# Low_Noise_100kHz_Oscilloscope_Preamplifi.net
KiCad netlist of a schematic drawn in Altium Designer
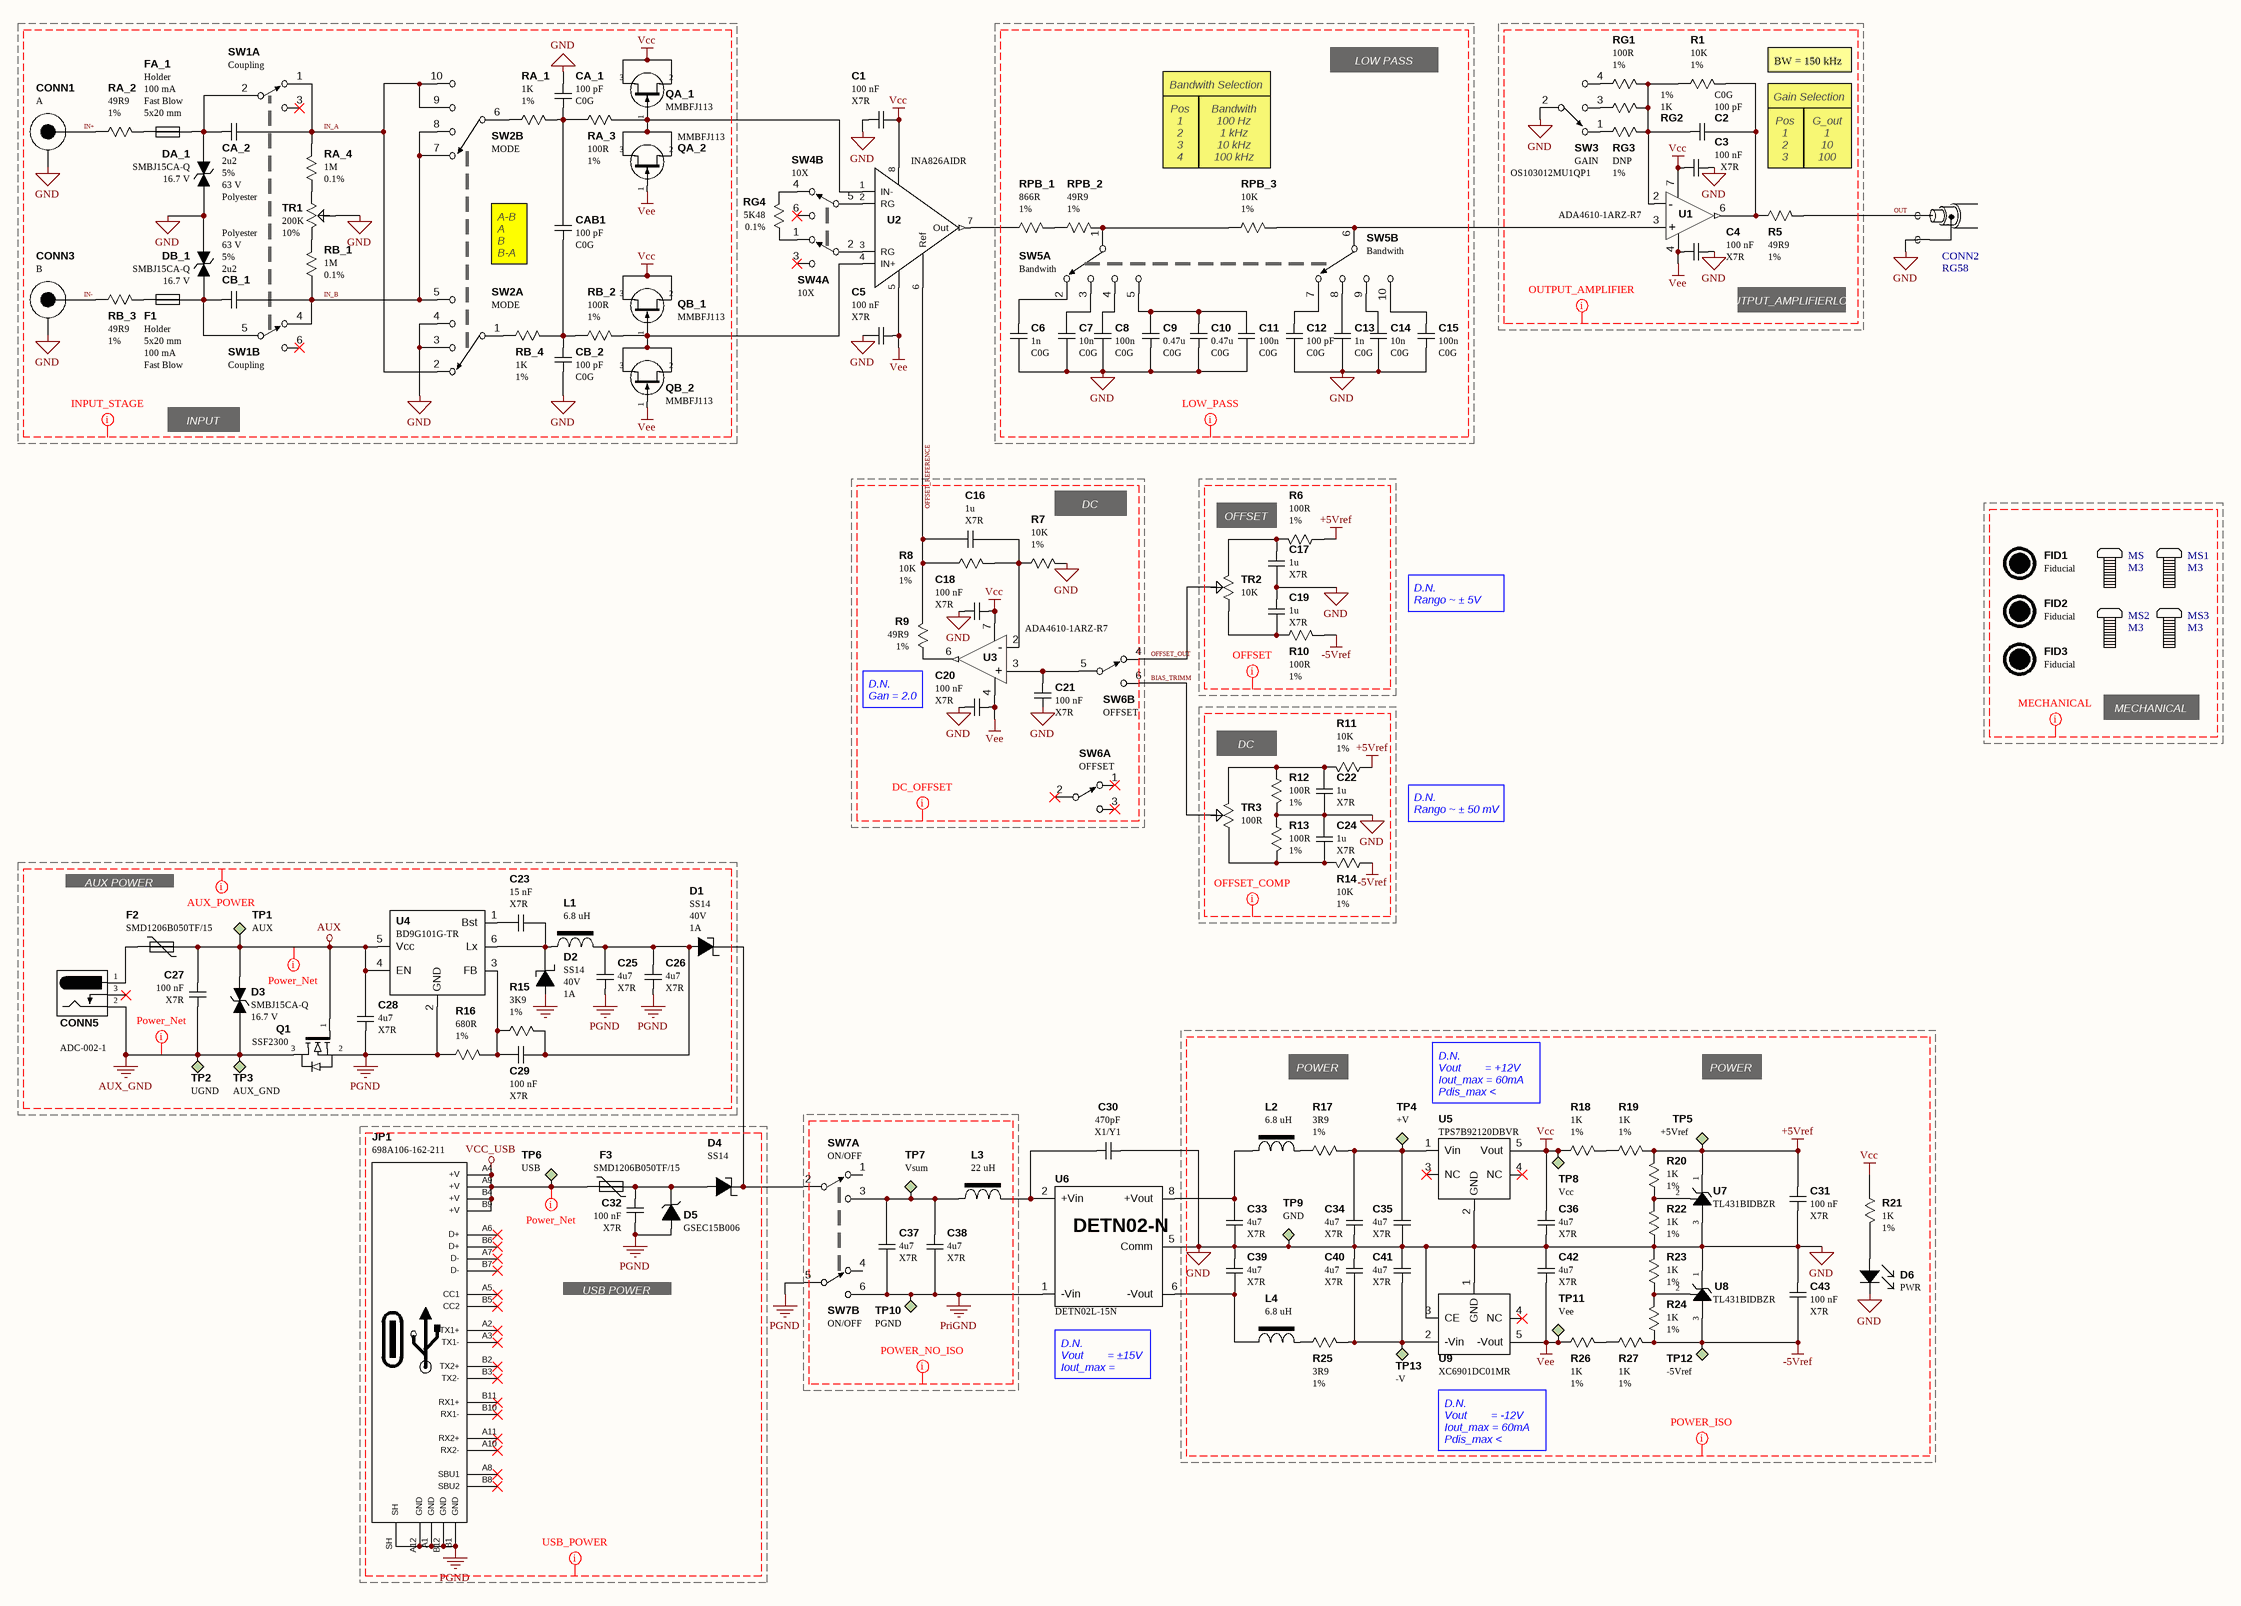
[diagram p0: Low_Noise_100kHz_Oscilloscope_Preamplifier.SchDoc]

(export (version "E")
  (design (tool "Eeschema 10.0.6"))
  (components
    (comp (ref "C1")
      (value "100 nF")
      (footprint "CAP_SMD_0603")
      (fields
        (field (name "04_MANUFACTURER PART NUMBER") "CC0603KRX7R9BB104")
        (field (name "05_DIGIKEY PART NUMBER") "311-1344-1-ND")
        (field (name "DIELECTRICO") "X7R")
      )
      (libsource (lib "Libreria_Altium") (part "Capacitor NP"))
    )
    (comp (ref "C2")
      (value "100 pF")
      (footprint "CAP_SMD_0603")
      (fields
        (field (name "04_MANUFACTURER PART NUMBER") "CC0603GRNPO9BN101")
        (field (name "05_DIGIKEY PART NUMBER") "311-3351-1-ND")
        (field (name "DIELECTRICO") "C0G")
      )
      (libsource (lib "Libreria_Altium") (part "Capacitor NP"))
    )
    (comp (ref "C3")
      (value "100 nF")
      (footprint "CAP_SMD_0603")
      (fields
        (field (name "04_MANUFACTURER PART NUMBER") "CC0603KRX7R9BB104")
        (field (name "05_DIGIKEY PART NUMBER") "311-1344-1-ND")
        (field (name "DIELECTRICO") "X7R")
      )
      (libsource (lib "Libreria_Altium") (part "Capacitor NP"))
    )
    (comp (ref "C4")
      (value "100 nF")
      (footprint "CAP_SMD_0603")
      (fields
        (field (name "04_MANUFACTURER PART NUMBER") "CC0603KRX7R9BB104")
        (field (name "05_DIGIKEY PART NUMBER") "311-1344-1-ND")
        (field (name "DIELECTRICO") "X7R")
      )
      (libsource (lib "Libreria_Altium") (part "Capacitor NP"))
    )
    (comp (ref "C5")
      (value "100 nF")
      (footprint "CAP_SMD_0603")
      (fields
        (field (name "04_MANUFACTURER PART NUMBER") "CC0603KRX7R9BB104")
        (field (name "05_DIGIKEY PART NUMBER") "311-1344-1-ND")
        (field (name "DIELECTRICO") "X7R")
      )
      (libsource (lib "Libreria_Altium") (part "Capacitor NP"))
    )
    (comp (ref "C6")
      (value "1n")
      (footprint "CAP_SMD_0603")
      (description "1000 pF ±2% 50V Ceramic Capacitor C0G, NP0 0603 (1608 Metric)")
      (fields
        (field (name "04_MANUFACTURER PART NUMBER") "CC0603GRNPO9BN102")
        (field (name "05_DIGIKEY PART NUMBER") "311-3916-1-ND")
        (field (name "DIELECTRICO") "C0G")
      )
      (libsource (lib "Libreria_Altium") (part "Capacitor NP"))
    )
    (comp (ref "C7")
      (value "10n")
      (footprint "CAP_SMD_0603")
      (description "10000 pF ±5% 50V Ceramic Capacitor C0G, NP0 0603 (1608 Metric)")
      (fields
        (field (name "04_MANUFACTURER PART NUMBER") "GRM1885C1H103JA01D")
        (field (name "05_DIGIKEY PART NUMBER") "490-9666-1-ND")
        (field (name "DIELECTRICO") "C0G")
      )
      (libsource (lib "Libreria_Altium") (part "Capacitor NP"))
    )
    (comp (ref "C8")
      (value "100n")
      (footprint "CAP_SMD_1206")
      (fields
        (field (name "04_MANUFACTURER PART NUMBER") "GRM3195C1H104JA05D")
        (field (name "05_DIGIKEY PART NUMBER") "490-GRM3195C1H104JA05DCT-ND")
        (field (name "DIELECTRICO") "C0G")
      )
      (libsource (lib "Libreria_Altium") (part "Capacitor NP"))
    )
    (comp (ref "C9")
      (value "0.47u")
      (footprint "CAP_SMD_1206")
      (description "0.47 µF ±5% 25V Ceramic Capacitor C0G, NP0 1206 (3216 Metric)")
      (fields
        (field (name "04_MANUFACTURER PART NUMBER") "GRM31C5C1E474JE01L")
        (field (name "05_DIGIKEY PART NUMBER") "490-GRM31C5C1E474JE01LCT-ND")
        (field (name "DIELECTRICO") "C0G")
      )
      (libsource (lib "Libreria_Altium") (part "Capacitor NP"))
    )
    (comp (ref "C10")
      (value "0.47u")
      (footprint "CAP_SMD_1206")
      (description "0.47 µF ±5% 25V Ceramic Capacitor C0G, NP0 1206 (3216 Metric)")
      (fields
        (field (name "04_MANUFACTURER PART NUMBER") "GRM31C5C1E474JE01L")
        (field (name "05_DIGIKEY PART NUMBER") "490-GRM31C5C1E474JE01LCT-ND")
        (field (name "DIELECTRICO") "C0G")
      )
      (libsource (lib "Libreria_Altium") (part "Capacitor NP"))
    )
    (comp (ref "C11")
      (value "100n")
      (footprint "CAP_SMD_1206")
      (fields
        (field (name "04_MANUFACTURER PART NUMBER") "GRM3195C1H104JA05D")
        (field (name "05_DIGIKEY PART NUMBER") "490-GRM3195C1H104JA05DCT-ND")
        (field (name "DIELECTRICO") "C0G")
      )
      (libsource (lib "Libreria_Altium") (part "Capacitor NP"))
    )
    (comp (ref "C12")
      (value "100 pF")
      (footprint "CAP_SMD_0603")
      (fields
        (field (name "04_MANUFACTURER PART NUMBER") "CC0603GRNPO9BN101")
        (field (name "05_DIGIKEY PART NUMBER") "311-3351-1-ND")
        (field (name "DIELECTRICO") "C0G")
      )
      (libsource (lib "Libreria_Altium") (part "Capacitor NP"))
    )
    (comp (ref "C13")
      (value "1n")
      (footprint "CAP_SMD_0603")
      (description "1000 pF ±2% 50V Ceramic Capacitor C0G, NP0 0603 (1608 Metric)")
      (fields
        (field (name "04_MANUFACTURER PART NUMBER") "CC0603GRNPO9BN102")
        (field (name "05_DIGIKEY PART NUMBER") "311-3916-1-ND")
        (field (name "DIELECTRICO") "C0G")
      )
      (libsource (lib "Libreria_Altium") (part "Capacitor NP"))
    )
    (comp (ref "C14")
      (value "10n")
      (footprint "CAP_SMD_0603")
      (description "10000 pF ±5% 50V Ceramic Capacitor C0G, NP0 0603 (1608 Metric)")
      (fields
        (field (name "04_MANUFACTURER PART NUMBER") "GRM1885C1H103JA01D")
        (field (name "05_DIGIKEY PART NUMBER") "490-9666-1-ND")
        (field (name "DIELECTRICO") "C0G")
      )
      (libsource (lib "Libreria_Altium") (part "Capacitor NP"))
    )
    (comp (ref "C15")
      (value "100n")
      (footprint "CAP_SMD_1206")
      (fields
        (field (name "04_MANUFACTURER PART NUMBER") "GRM3195C1H104JA05D")
        (field (name "05_DIGIKEY PART NUMBER") "490-GRM3195C1H104JA05DCT-ND")
        (field (name "DIELECTRICO") "C0G")
      )
      (libsource (lib "Libreria_Altium") (part "Capacitor NP"))
    )
    (comp (ref "C16")
      (value "1u")
      (footprint "CAP_SMD_0805")
      (fields
        (field (name "04_MANUFACTURER PART NUMBER") "CC0805JKX7R9BB105")
        (field (name "05_DIGIKEY PART NUMBER") "311-3498-1-ND")
        (field (name "DIELECTRICO") "X7R")
      )
      (libsource (lib "Libreria_Altium") (part "Capacitor NP"))
    )
    (comp (ref "C17")
      (value "1u")
      (footprint "CAP_SMD_0805")
      (fields
        (field (name "04_MANUFACTURER PART NUMBER") "CC0805JKX7R9BB105")
        (field (name "05_DIGIKEY PART NUMBER") "311-3498-1-ND")
        (field (name "DIELECTRICO") "X7R")
      )
      (libsource (lib "Libreria_Altium") (part "Capacitor NP"))
    )
    (comp (ref "C18")
      (value "100 nF")
      (footprint "CAP_SMD_0603")
      (fields
        (field (name "04_MANUFACTURER PART NUMBER") "CC0603KRX7R9BB104")
        (field (name "05_DIGIKEY PART NUMBER") "311-1344-1-ND")
        (field (name "DIELECTRICO") "X7R")
      )
      (libsource (lib "Libreria_Altium") (part "Capacitor NP"))
    )
    (comp (ref "C19")
      (value "1u")
      (footprint "CAP_SMD_0805")
      (fields
        (field (name "04_MANUFACTURER PART NUMBER") "CC0805JKX7R9BB105")
        (field (name "05_DIGIKEY PART NUMBER") "311-3498-1-ND")
        (field (name "DIELECTRICO") "X7R")
      )
      (libsource (lib "Libreria_Altium") (part "Capacitor NP"))
    )
    (comp (ref "C20")
      (value "100 nF")
      (footprint "CAP_SMD_0603")
      (fields
        (field (name "04_MANUFACTURER PART NUMBER") "CC0603KRX7R9BB104")
        (field (name "05_DIGIKEY PART NUMBER") "311-1344-1-ND")
        (field (name "DIELECTRICO") "X7R")
      )
      (libsource (lib "Libreria_Altium") (part "Capacitor NP"))
    )
    (comp (ref "C21")
      (value "100 nF")
      (footprint "CAP_SMD_0603")
      (fields
        (field (name "04_MANUFACTURER PART NUMBER") "CC0603KRX7R9BB104")
        (field (name "05_DIGIKEY PART NUMBER") "311-1344-1-ND")
        (field (name "DIELECTRICO") "X7R")
      )
      (libsource (lib "Libreria_Altium") (part "Capacitor NP"))
    )
    (comp (ref "C22")
      (value "1u")
      (footprint "CAP_SMD_0805")
      (fields
        (field (name "04_MANUFACTURER PART NUMBER") "CC0805JKX7R9BB105")
        (field (name "05_DIGIKEY PART NUMBER") "311-3498-1-ND")
        (field (name "DIELECTRICO") "X7R")
      )
      (libsource (lib "Libreria_Altium") (part "Capacitor NP"))
    )
    (comp (ref "C23")
      (value "15 nF")
      (footprint "CAP_SMD_0603")
      (description "0.1 µF ±10% 25V Ceramic Capacitor X7R 0603 (1608 Metric)")
      (fields
        (field (name "04_MANUFACTURER PART NUMBER") "CC0603KRX7R9BB153")
        (field (name "05_DIGIKEY PART NUMBER") "311-1430-1-ND")
        (field (name "DIELECTRICO") "X7R")
      )
      (libsource (lib "Libreria_Altium") (part "Capacitor NP"))
    )
    (comp (ref "C24")
      (value "1u")
      (footprint "CAP_SMD_0805")
      (fields
        (field (name "04_MANUFACTURER PART NUMBER") "CC0805JKX7R9BB105")
        (field (name "05_DIGIKEY PART NUMBER") "311-3498-1-ND")
        (field (name "DIELECTRICO") "X7R")
      )
      (libsource (lib "Libreria_Altium") (part "Capacitor NP"))
    )
    (comp (ref "C25")
      (value "4u7")
      (footprint "CAP_SMD_0805")
      (description "4.7 µF ±20% 50V Ceramic Capacitor X7R 0805 (2012 Metric)")
      (fields
        (field (name "04_MANUFACTURER PART NUMBER") "GRM21BZ71H475ME15K")
        (field (name "05_DIGIKEY PART NUMBER") "490-GRM21BZ71H475ME15KCT-ND")
        (field (name "DIELECTRICO") "X7R")
      )
      (libsource (lib "Libreria_Altium") (part "Capacitor NP"))
    )
    (comp (ref "C26")
      (value "4u7")
      (footprint "CAP_SMD_0805")
      (description "4.7 µF ±20% 50V Ceramic Capacitor X7R 0805 (2012 Metric)")
      (fields
        (field (name "04_MANUFACTURER PART NUMBER") "GRM21BZ71H475ME15K")
        (field (name "05_DIGIKEY PART NUMBER") "490-GRM21BZ71H475ME15KCT-ND")
        (field (name "DIELECTRICO") "X7R")
      )
      (libsource (lib "Libreria_Altium") (part "Capacitor NP"))
    )
    (comp (ref "C27")
      (value "100 nF")
      (footprint "CAP_SMD_0603")
      (description "0.1 µF ±10% 25V Ceramic Capacitor X7R 0603 (1608 Metric)")
      (fields
        (field (name "04_MANUFACTURER PART NUMBER") "CC0603KRX7R9BB104")
        (field (name "05_DIGIKEY PART NUMBER") "311-1344-1-ND")
        (field (name "DIELECTRICO") "X7R")
      )
      (libsource (lib "Libreria_Altium") (part "Capacitor NP"))
    )
    (comp (ref "C28")
      (value "4u7")
      (footprint "CAP_SMD_0805")
      (description "4.7 µF ±20% 50V Ceramic Capacitor X7R 0805 (2012 Metric)")
      (fields
        (field (name "04_MANUFACTURER PART NUMBER") "GRM21BZ71H475ME15K")
        (field (name "05_DIGIKEY PART NUMBER") "490-GRM21BZ71H475ME15KCT-ND")
        (field (name "DIELECTRICO") "X7R")
      )
      (libsource (lib "Libreria_Altium") (part "Capacitor NP"))
    )
    (comp (ref "C29")
      (value "100 nF")
      (footprint "CAP_SMD_0603")
      (description "0.1 µF ±10% 25V Ceramic Capacitor X7R 0603 (1608 Metric)")
      (fields
        (field (name "04_MANUFACTURER PART NUMBER") "CC0603KRX7R9BB104")
        (field (name "05_DIGIKEY PART NUMBER") "311-1344-1-ND")
        (field (name "DIELECTRICO") "X7R")
      )
      (libsource (lib "Libreria_Altium") (part "Capacitor NP"))
    )
    (comp (ref "C30")
      (value "470pF")
      (footprint "Capacitor_Radial_7.00mm")
      (description "470 pF ±10% 1500V (1.5kV) Ceramic Capacitor B Radial, Disc")
      (fields
        (field (name "04_MANUFACTURER PART NUMBER") "DE1B3RA471KN4AP01F")
        (field (name "05_DIGIKEY PART NUMBER") "490-16186-1-ND")
        (field (name "DIELECTRICO") "X1/Y1")
      )
      (libsource (lib "Libreria_Altium") (part "Capacitor NP"))
    )
    (comp (ref "C31")
      (value "100 nF")
      (footprint "CAP_SMD_0603")
      (fields
        (field (name "04_MANUFACTURER PART NUMBER") "CC0603KRX7R9BB104")
        (field (name "05_DIGIKEY PART NUMBER") "311-1344-1-ND")
        (field (name "DIELECTRICO") "X7R")
      )
      (libsource (lib "Libreria_Altium") (part "Capacitor NP"))
    )
    (comp (ref "C32")
      (value "100 nF")
      (footprint "CAP_SMD_0603")
      (description "0.1 µF ±10% 25V Ceramic Capacitor X7R 0603 (1608 Metric)")
      (fields
        (field (name "04_MANUFACTURER PART NUMBER") "CC0603KRX7R9BB104")
        (field (name "05_DIGIKEY PART NUMBER") "311-1344-1-ND")
        (field (name "DIELECTRICO") "X7R")
      )
      (libsource (lib "Libreria_Altium") (part "Capacitor NP"))
    )
    (comp (ref "C33")
      (value "4u7")
      (footprint "CAP_SMD_0805")
      (description "4.7 µF ±20% 50V Ceramic Capacitor X7R 0805 (2012 Metric)")
      (fields
        (field (name "04_MANUFACTURER PART NUMBER") "GRM21BZ71H475ME15K")
        (field (name "05_DIGIKEY PART NUMBER") "490-GRM21BZ71H475ME15KCT-ND")
        (field (name "DIELECTRICO") "X7R")
      )
      (libsource (lib "Libreria_Altium") (part "Capacitor NP"))
    )
    (comp (ref "C34")
      (value "4u7")
      (footprint "CAP_SMD_0805")
      (description "4.7 µF ±20% 50V Ceramic Capacitor X7R 0805 (2012 Metric)")
      (fields
        (field (name "04_MANUFACTURER PART NUMBER") "GRM21BZ71H475ME15K")
        (field (name "05_DIGIKEY PART NUMBER") "490-GRM21BZ71H475ME15KCT-ND")
        (field (name "DIELECTRICO") "X7R")
      )
      (libsource (lib "Libreria_Altium") (part "Capacitor NP"))
    )
    (comp (ref "C35")
      (value "4u7")
      (footprint "CAP_SMD_0805")
      (description "4.7 µF ±20% 50V Ceramic Capacitor X7R 0805 (2012 Metric)")
      (fields
        (field (name "04_MANUFACTURER PART NUMBER") "GRM21BZ71H475ME15K")
        (field (name "05_DIGIKEY PART NUMBER") "490-GRM21BZ71H475ME15KCT-ND")
        (field (name "DIELECTRICO") "X7R")
      )
      (libsource (lib "Libreria_Altium") (part "Capacitor NP"))
    )
    (comp (ref "C36")
      (value "4u7")
      (footprint "CAP_SMD_0805")
      (description "4.7 µF ±20% 50V Ceramic Capacitor X7R 0805 (2012 Metric)")
      (fields
        (field (name "04_MANUFACTURER PART NUMBER") "GRM21BZ71H475ME15K")
        (field (name "05_DIGIKEY PART NUMBER") "490-GRM21BZ71H475ME15KCT-ND")
        (field (name "DIELECTRICO") "X7R")
      )
      (libsource (lib "Libreria_Altium") (part "Capacitor NP"))
    )
    (comp (ref "C37")
      (value "4u7")
      (footprint "CAP_SMD_0805")
      (description "4.7 µF ±20% 50V Ceramic Capacitor X7R 0805 (2012 Metric)")
      (fields
        (field (name "04_MANUFACTURER PART NUMBER") "GRM21BZ71H475ME15K")
        (field (name "05_DIGIKEY PART NUMBER") "490-GRM21BZ71H475ME15KCT-ND")
        (field (name "DIELECTRICO") "X7R")
      )
      (libsource (lib "Libreria_Altium") (part "Capacitor NP"))
    )
    (comp (ref "C38")
      (value "4u7")
      (footprint "CAP_SMD_0805")
      (description "4.7 µF ±20% 50V Ceramic Capacitor X7R 0805 (2012 Metric)")
      (fields
        (field (name "04_MANUFACTURER PART NUMBER") "GRM21BZ71H475ME15K")
        (field (name "05_DIGIKEY PART NUMBER") "490-GRM21BZ71H475ME15KCT-ND")
        (field (name "DIELECTRICO") "X7R")
      )
      (libsource (lib "Libreria_Altium") (part "Capacitor NP"))
    )
    (comp (ref "C39")
      (value "4u7")
      (footprint "CAP_SMD_0805")
      (description "4.7 µF ±20% 50V Ceramic Capacitor X7R 0805 (2012 Metric)")
      (fields
        (field (name "04_MANUFACTURER PART NUMBER") "GRM21BZ71H475ME15K")
        (field (name "05_DIGIKEY PART NUMBER") "490-GRM21BZ71H475ME15KCT-ND")
        (field (name "DIELECTRICO") "X7R")
      )
      (libsource (lib "Libreria_Altium") (part "Capacitor NP"))
    )
    (comp (ref "C40")
      (value "4u7")
      (footprint "CAP_SMD_0805")
      (description "4.7 µF ±20% 50V Ceramic Capacitor X7R 0805 (2012 Metric)")
      (fields
        (field (name "04_MANUFACTURER PART NUMBER") "GRM21BZ71H475ME15K")
        (field (name "05_DIGIKEY PART NUMBER") "490-GRM21BZ71H475ME15KCT-ND")
        (field (name "DIELECTRICO") "X7R")
      )
      (libsource (lib "Libreria_Altium") (part "Capacitor NP"))
    )
    (comp (ref "C41")
      (value "4u7")
      (footprint "CAP_SMD_0805")
      (description "4.7 µF ±20% 50V Ceramic Capacitor X7R 0805 (2012 Metric)")
      (fields
        (field (name "04_MANUFACTURER PART NUMBER") "GRM21BZ71H475ME15K")
        (field (name "05_DIGIKEY PART NUMBER") "490-GRM21BZ71H475ME15KCT-ND")
        (field (name "DIELECTRICO") "X7R")
      )
      (libsource (lib "Libreria_Altium") (part "Capacitor NP"))
    )
    (comp (ref "C42")
      (value "4u7")
      (footprint "CAP_SMD_0805")
      (description "4.7 µF ±20% 50V Ceramic Capacitor X7R 0805 (2012 Metric)")
      (fields
        (field (name "04_MANUFACTURER PART NUMBER") "GRM21BZ71H475ME15K")
        (field (name "05_DIGIKEY PART NUMBER") "490-GRM21BZ71H475ME15KCT-ND")
        (field (name "DIELECTRICO") "X7R")
      )
      (libsource (lib "Libreria_Altium") (part "Capacitor NP"))
    )
    (comp (ref "C43")
      (value "100 nF")
      (footprint "CAP_SMD_0603")
      (fields
        (field (name "04_MANUFACTURER PART NUMBER") "CC0603KRX7R9BB104")
        (field (name "05_DIGIKEY PART NUMBER") "311-1344-1-ND")
        (field (name "DIELECTRICO") "X7R")
      )
      (libsource (lib "Libreria_Altium") (part "Capacitor NP"))
    )
    (comp (ref "CAB1")
      (value "100 pF")
      (footprint "CAP_SMD_0603")
      (fields
        (field (name "04_MANUFACTURER PART NUMBER") "CC0603GRNPO9BN101")
        (field (name "05_DIGIKEY PART NUMBER") "311-3351-1-ND")
        (field (name "DIELECTRICO") "C0G")
      )
      (libsource (lib "Libreria_Altium") (part "Capacitor NP"))
    )
    (comp (ref "CA_1")
      (value "100 pF")
      (footprint "CAP_SMD_0603")
      (fields
        (field (name "04_MANUFACTURER PART NUMBER") "CC0603GRNPO9BN101")
        (field (name "05_DIGIKEY PART NUMBER") "311-3351-1-ND")
        (field (name "DIELECTRICO") "C0G")
      )
      (libsource (lib "Libreria_Altium") (part "Capacitor NP"))
    )
    (comp (ref "CA_2")
      (value "2u2")
      (footprint "Capacitor_7.8x7.8x13")
      (fields
        (field (name "04_MANUFACTURER PART NUMBER") "B32529D0225J000")
        (field (name "05_DIGIKEY PART NUMBER") "495-1127-ND")
        (field (name "TOLERANCIA") "5%")
        (field (name "TENSIÓN") "63 V")
        (field (name "DIELECTRICO") "Polyester")
      )
      (libsource (lib "Libreria_Altium") (part "Capacitor NP"))
    )
    (comp (ref "CB_1")
      (value "2u2")
      (footprint "Capacitor_7.8x7.8x13")
      (fields
        (field (name "04_MANUFACTURER PART NUMBER") "B32529D0225J000")
        (field (name "05_DIGIKEY PART NUMBER") "495-1127-ND")
        (field (name "TOLERANCIA") "5%")
        (field (name "TENSIÓN") "63 V")
        (field (name "DIELECTRICO") "Polyester")
      )
      (libsource (lib "Libreria_Altium") (part "Capacitor NP"))
    )
    (comp (ref "CB_2")
      (value "100 pF")
      (footprint "CAP_SMD_0603")
      (fields
        (field (name "04_MANUFACTURER PART NUMBER") "CC0603GRNPO9BN101")
        (field (name "05_DIGIKEY PART NUMBER") "311-3351-1-ND")
        (field (name "DIELECTRICO") "C0G")
      )
      (libsource (lib "Libreria_Altium") (part "Capacitor NP"))
    )
    (comp (ref "CONN1")
      (value "A")
      (footprint "CONBNC002")
      (description "BNC Connector Jack, Female Socket 50 Ohms Panel Mount, Through Hole, Right Angle Solder")
      (fields
        (field (name "04_MANUFACTURER PART NUMBER") "CONBNC002")
        (field (name "05_DIGIKEY PART NUMBER") "343-CONBNC002-ND")
      )
      (libsource (lib "Libreria_Altium") (part "Conector BNC"))
    )
    (comp (ref "CONN2")
      (value "RG58")
      (footprint "Coaxial_RG58")
      (description "Cable RG58 Soldado directo a PCB")
      (libsource (lib "Libreria_Altium") (part "RG58_Coaxial_Cable"))
    )
    (comp (ref "CONN3")
      (value "B")
      (footprint "CONBNC002")
      (description "BNC Connector Jack, Female Socket 50 Ohms Panel Mount, Through Hole, Right Angle Solder")
      (fields
        (field (name "04_MANUFACTURER PART NUMBER") "CONBNC002")
        (field (name "05_DIGIKEY PART NUMBER") "343-CONBNC002-ND")
      )
      (libsource (lib "Libreria_Altium") (part "Conector BNC"))
    )
    (comp (ref "CONN5")
      (value "AUX")
      (footprint "ADC-002A")
      (description "DC JACK")
      (fields
        (field (name "04_MANUFACTURER PART NUMBER") "ADC-002-1")
        (field (name "05_DIGIKEY PART NUMBER") "2057-ADC-002-1-ND")
      )
      (libsource (lib "Libreria_Altium") (part "DC JACK"))
    )
    (comp (ref "D1")
      (value "SS14")
      (footprint "DO_214_AC")
      (description "Diode 40 V 1A Surface Mount DO-214AC (SMA)")
      (fields
        (field (name "04_MANUFACTURER PART NUMBER") "SS14-M3/5AT")
        (field (name "05_DIGIKEY PART NUMBER") "SS14-M3/5ATGICT-ND")
        (field (name "TENSIÓN") "40V")
        (field (name "CORRIENTE") "1A")
      )
      (libsource (lib "Libreria_Altium") (part "Diodo Schottky"))
    )
    (comp (ref "D2")
      (value "SS14")
      (footprint "DO_214_AC")
      (description "Diode 40 V 1A Surface Mount DO-214AC (SMA)")
      (fields
        (field (name "04_MANUFACTURER PART NUMBER") "SS14-M3/5AT")
        (field (name "05_DIGIKEY PART NUMBER") "SS14-M3/5ATGICT-ND")
        (field (name "TENSIÓN") "40V")
        (field (name "CORRIENTE") "1A")
      )
      (libsource (lib "Libreria_Altium") (part "Diodo Schottky"))
    )
    (comp (ref "D3")
      (value "SMBJ15CA-Q")
      (footprint "SOD_323")
      (description "24.4V Clamp 24.6A Ipp Tvs Diode Surface Mount DO-214AA (SMB)")
      (fields (field (name "05_DIGIKEY PART NUMBER") "118-SMBJ15CA-QCT-ND") (field (name "TENSIÓN") "16.7 V"))
      (libsource (lib "Libreria_Altium") (part "Diodo TVS Bidireccional"))
    )
    (comp (ref "D4")
      (value "SS14")
      (footprint "DO_214_AC")
      (description "Diode 40 V 1A Surface Mount DO-214AC (SMA)")
      (fields
        (field (name "04_MANUFACTURER PART NUMBER") "SS14-M3/5AT")
        (field (name "05_DIGIKEY PART NUMBER") "SS14-M3/5ATGICT-ND")
      )
      (libsource (lib "Libreria_Altium") (part "Diodo Schottky"))
    )
    (comp (ref "D5")
      (value "GSEC15B006")
      (footprint "SOD_323")
      (description "Diodo TVS")
      (fields (field (name "05_DIGIKEY PART NUMBER") "4786-GSEC15B006CT-ND"))
      (libsource (lib "Libreria_Altium") (part "Diodo TVS Unidireccional"))
    )
    (comp (ref "D6")
      (value "PWR")
      (footprint "LED_0603_1608")
      (description "Diodo LEd")
      (fields
        (field (name "04_MANUFACTURER PART NUMBER") "SML-D12U1WT86")
        (field (name "05_DIGIKEY PART NUMBER") "SML-D12U1WT86CT-ND")
      )
      (libsource (lib "Libreria_Altium") (part "Diodo LED"))
    )
    (comp (ref "DA_1")
      (value "SMBJ15CA-Q")
      (footprint "SOD_323")
      (description "24.4V Clamp 24.6A Ipp Tvs Diode Surface Mount DO-214AA (SMB)")
      (fields (field (name "05_DIGIKEY PART NUMBER") "118-SMBJ15CA-QCT-ND") (field (name "TENSIÓN") "16.7 V"))
      (libsource (lib "Libreria_Altium") (part "Diodo TVS Bidireccional"))
    )
    (comp (ref "DB_1")
      (value "SMBJ15CA-Q")
      (footprint "SOD_323")
      (description "24.4V Clamp 24.6A Ipp Tvs Diode Surface Mount DO-214AA (SMB)")
      (fields (field (name "05_DIGIKEY PART NUMBER") "118-SMBJ15CA-QCT-ND") (field (name "TENSIÓN") "16.7 V"))
      (libsource (lib "Libreria_Altium") (part "Diodo TVS Bidireccional"))
    )
    (comp (ref "F1")
      (value "Holder")
      (footprint "Porta Fusible 15x20")
      (description "Fuse Block 20 A 250V 1 Circuit Cartridge Through Hole")
      (fields
        (field (name "03_ENCAPSULADO") "5x20 mm")
        (field (name "04_MANUFACTURER PART NUMBER") "952017100001000")
        (field (name "05_DIGIKEY PART NUMBER") "732-952017100001000-ND")
        (field (name "CORRIENTE") "100 mA")
        (field (name "P_TYPE") "Fast Blow")
      )
      (libsource (lib "Libreria_Altium") (part "Fusible"))
    )
    (comp (ref "F2")
      (value "SMD1206B050TF/15")
      (footprint "RES_SMD_1210")
      (description "Polymeric PTC Resettable Fuse 15V 500 mA Ih Surface Mount 1206 (3216 Metric), Concave")
      (fields
        (field (name "04_MANUFACTURER PART NUMBER") "SMD1206B025TF/24")
        (field (name "05_DIGIKEY PART NUMBER") "13-SMD1206B025TF/24CT-ND")
      )
      (libsource (lib "Libreria_Altium") (part "Polyswitch"))
    )
    (comp (ref "F3")
      (value "SMD1206B050TF/15")
      (footprint "RES_SMD_1210")
      (description "Polymeric PTC Resettable Fuse 15V 500 mA Ih Surface Mount 1206 (3216 Metric), Concave")
      (fields
        (field (name "04_MANUFACTURER PART NUMBER") "SMD1206B025TF/24")
        (field (name "05_DIGIKEY PART NUMBER") "13-SMD1206B025TF/24CT-ND")
      )
      (libsource (lib "Libreria_Altium") (part "Polyswitch"))
    )
    (comp (ref "FA_1")
      (value "Holder")
      (footprint "Porta Fusible 15x20")
      (description "Fuse Block 20 A 250V 1 Circuit Cartridge Through Hole")
      (fields
        (field (name "03_ENCAPSULADO") "5x20 mm")
        (field (name "04_MANUFACTURER PART NUMBER") "952017100001000")
        (field (name "05_DIGIKEY PART NUMBER") "732-952017100001000-ND")
        (field (name "CORRIENTE") "100 mA")
        (field (name "P_TYPE") "Fast Blow")
      )
      (libsource (lib "Libreria_Altium") (part "Fusible"))
    )
    (comp (ref "FID1")
      (value "Fiducial")
      (footprint "Fiducial")
      (description "Fiducial SMD")
      (libsource (lib "Libreria_Altium") (part "Fiducial"))
    )
    (comp (ref "FID2")
      (value "Fiducial")
      (footprint "Fiducial")
      (description "Fiducial SMD")
      (libsource (lib "Libreria_Altium") (part "Fiducial"))
    )
    (comp (ref "FID3")
      (value "Fiducial")
      (footprint "Fiducial")
      (description "Fiducial SMD")
      (libsource (lib "Libreria_Altium") (part "Fiducial"))
    )
    (comp (ref "JP1")
      (value "698A106-162-211")
      (footprint "1054500101")
      (fields
        (field (name "04_MANUFACTURER PART NUMBER") "1054500101")
        (field (name "05_DIGIKEY PART NUMBER") "WM12856CT-ND")
      )
      (libsource (lib "Libreria_Altium") (part "USB C 3.0"))
    )
    (comp (ref "L1")
      (value "6.8 uH")
      (footprint "IND_SMD_6.0x6.0x4.5")
      (description "6.8 µH Shielded Wirewound Inductor 2.8 A 38mOhm Max 2424 (6060 Metric)")
      (fields
        (field (name "04_MANUFACTURER PART NUMBER") "IFSC2020DEER6R8M01")
        (field (name "05_DIGIKEY PART NUMBER") "541-IFSC2020DEER6R8M01CT-ND")
      )
      (libsource (lib "Libreria_Altium") (part "Inductor"))
    )
    (comp (ref "L2")
      (value "6.8 uH")
      (footprint "IND_SMD_6.0x6.0x4.5")
      (description "6.8 µH Shielded Wirewound Inductor 2.8 A 38mOhm Max 2424 (6060 Metric)")
      (fields
        (field (name "04_MANUFACTURER PART NUMBER") "IFSC2020DEER6R8M01")
        (field (name "05_DIGIKEY PART NUMBER") "541-IFSC2020DEER6R8M01CT-ND")
      )
      (libsource (lib "Libreria_Altium") (part "Inductor"))
    )
    (comp (ref "L3")
      (value "22 uH")
      (footprint "IND_SMD_12.7x12.7x6.5")
      (description "22 µH Shielded Drum Core, Wirewound Inductor 2.3 A 62mOhm Max Nonstandard")
      (fields
        (field (name "04_MANUFACTURER PART NUMBER") "SRR1206-220ML")
        (field (name "05_DIGIKEY PART NUMBER") "SRR1206-220MLCT-ND")
      )
      (libsource (lib "Libreria_Altium") (part "Inductor"))
    )
    (comp (ref "L4")
      (value "6.8 uH")
      (footprint "IND_SMD_6.0x6.0x4.5")
      (description "6.8 µH Shielded Wirewound Inductor 2.8 A 38mOhm Max 2424 (6060 Metric)")
      (fields
        (field (name "04_MANUFACTURER PART NUMBER") "IFSC2020DEER6R8M01")
        (field (name "05_DIGIKEY PART NUMBER") "541-IFSC2020DEER6R8M01CT-ND")
      )
      (libsource (lib "Libreria_Altium") (part "Inductor"))
    )
    (comp (ref "MS")
      (value "M3")
      (footprint "Fiducial")
      (description "Tornillo M3")
      (libsource (lib "Libreria_Altium") (part "Tornillo M3"))
    )
    (comp (ref "MS1")
      (value "M3")
      (footprint "Fiducial")
      (description "Tornillo M3")
      (libsource (lib "Libreria_Altium") (part "Tornillo M3"))
    )
    (comp (ref "MS2")
      (value "M3")
      (footprint "Fiducial")
      (description "Tornillo M3")
      (libsource (lib "Libreria_Altium") (part "Tornillo M3"))
    )
    (comp (ref "MS3")
      (value "M3")
      (footprint "Fiducial")
      (description "Tornillo M3")
      (libsource (lib "Libreria_Altium") (part "Tornillo M3"))
    )
    (comp (ref "Q1")
      (value "SSF2300")
      (footprint "SOT_23-3")
      (description "N-Channel MOSFET SOT-23")
      (fields
        (field (name "04_MANUFACTURER PART NUMBER") "AO3414A")
        (field (name "05_DIGIKEY PART NUMBER") "4518-AO3414ACT-ND")
      )
      (libsource (lib "Libreria_Altium") (part "NMOS"))
    )
    (comp (ref "QA_1")
      (value "MMBFJ113")
      (footprint "SOT_23-3")
      (description "JFET N-Channel 35 V 350 mW Surface Mount SOT-23-3")
      (fields (field (name "05_DIGIKEY PART NUMBER") "MMBFJ113CT-ND"))
      (libsource (lib "Libreria_Altium") (part "JFET"))
    )
    (comp (ref "QA_2")
      (value "MMBFJ113")
      (footprint "SOT_23-3")
      (description "JFET N-Channel 35 V 350 mW Surface Mount SOT-23-3")
      (fields (field (name "05_DIGIKEY PART NUMBER") "MMBFJ113CT-ND"))
      (libsource (lib "Libreria_Altium") (part "JFET"))
    )
    (comp (ref "QB_1")
      (value "MMBFJ113")
      (footprint "SOT_23-3")
      (description "JFET N-Channel 35 V 350 mW Surface Mount SOT-23-3")
      (fields (field (name "05_DIGIKEY PART NUMBER") "MMBFJ113CT-ND"))
      (libsource (lib "Libreria_Altium") (part "JFET"))
    )
    (comp (ref "QB_2")
      (value "MMBFJ113")
      (footprint "SOT_23-3")
      (description "JFET N-Channel 35 V 350 mW Surface Mount SOT-23-3")
      (fields (field (name "05_DIGIKEY PART NUMBER") "MMBFJ113CT-ND"))
      (libsource (lib "Libreria_Altium") (part "JFET"))
    )
    (comp (ref "R1")
      (value "10K")
      (footprint "RES_SMD_0603")
      (description "10 kOhms ±1% 0.1W, 1/10W Chip Resistor 0603 (1608 Metric) Thin Film")
      (fields
        (field (name "04_MANUFACTURER PART NUMBER") "RT0603FRE0710KL")
        (field (name "05_DIGIKEY PART NUMBER") "YAG2321CT-ND")
        (field (name "TOLERANCIA") "1%")
      )
      (libsource (lib "Libreria_Altium") (part "Resistor"))
    )
    (comp (ref "R5")
      (value "49R9")
      (footprint "RES_SMD_0603")
      (description "49.9 Ohms ±1% 0.1W, 1/10W Chip Resistor 0603 (1608 Metric) Thin Film")
      (fields
        (field (name "04_MANUFACTURER PART NUMBER") "RT0603FRD0749R9L")
        (field (name "05_DIGIKEY PART NUMBER") "13-RT0603FRD0749R9LCT-ND")
        (field (name "TOLERANCIA") "1%")
      )
      (libsource (lib "Libreria_Altium") (part "Resistor"))
    )
    (comp (ref "R6")
      (value "100R")
      (footprint "RES_SMD_0603")
      (description "100 Ohms ±1% 0.1W, 1/10W Chip Resistor 0603 (1608 Metric) Thin Film")
      (fields
        (field (name "04_MANUFACTURER PART NUMBER") "RT0603FRE13100RL")
        (field (name "05_DIGIKEY PART NUMBER") "13-RT0603FRE13100RLCT-ND")
        (field (name "TOLERANCIA") "1%")
      )
      (libsource (lib "Libreria_Altium") (part "Resistor"))
    )
    (comp (ref "R7")
      (value "10K")
      (footprint "RES_SMD_0603")
      (description "10 kOhms ±1% 0.1W, 1/10W Chip Resistor 0603 (1608 Metric) Thin Film")
      (fields
        (field (name "04_MANUFACTURER PART NUMBER") "RT0603FRE0710KL")
        (field (name "05_DIGIKEY PART NUMBER") "YAG2321CT-ND")
        (field (name "TOLERANCIA") "1%")
      )
      (libsource (lib "Libreria_Altium") (part "Resistor"))
    )
    (comp (ref "R8")
      (value "10K")
      (footprint "RES_SMD_0603")
      (description "10 kOhms ±1% 0.1W, 1/10W Chip Resistor 0603 (1608 Metric) Thin Film")
      (fields
        (field (name "04_MANUFACTURER PART NUMBER") "RT0603FRE0710KL")
        (field (name "05_DIGIKEY PART NUMBER") "YAG2321CT-ND")
        (field (name "TOLERANCIA") "1%")
      )
      (libsource (lib "Libreria_Altium") (part "Resistor"))
    )
    (comp (ref "R9")
      (value "49R9")
      (footprint "RES_SMD_0603")
      (description "49.9 Ohms ±1% 0.1W, 1/10W Chip Resistor 0603 (1608 Metric) Thin Film")
      (fields
        (field (name "04_MANUFACTURER PART NUMBER") "RT0603FRD0749R9L")
        (field (name "05_DIGIKEY PART NUMBER") "13-RT0603FRD0749R9LCT-ND")
        (field (name "TOLERANCIA") "1%")
      )
      (libsource (lib "Libreria_Altium") (part "Resistor"))
    )
    (comp (ref "R10")
      (value "100R")
      (footprint "RES_SMD_0603")
      (description "100 Ohms ±1% 0.1W, 1/10W Chip Resistor 0603 (1608 Metric) Thin Film")
      (fields
        (field (name "04_MANUFACTURER PART NUMBER") "RT0603FRE13100RL")
        (field (name "05_DIGIKEY PART NUMBER") "13-RT0603FRE13100RLCT-ND")
        (field (name "TOLERANCIA") "1%")
      )
      (libsource (lib "Libreria_Altium") (part "Resistor"))
    )
    (comp (ref "R11")
      (value "10K")
      (footprint "RES_SMD_0603")
      (description "10 kOhms ±1% 0.1W, 1/10W Chip Resistor 0603 (1608 Metric) Thin Film")
      (fields
        (field (name "04_MANUFACTURER PART NUMBER") "RT0603FRE0710KL")
        (field (name "05_DIGIKEY PART NUMBER") "YAG2321CT-ND")
        (field (name "TOLERANCIA") "1%")
      )
      (libsource (lib "Libreria_Altium") (part "Resistor"))
    )
    (comp (ref "R12")
      (value "100R")
      (footprint "RES_SMD_0603")
      (description "100 Ohms ±1% 0.1W, 1/10W Chip Resistor 0603 (1608 Metric) Thin Film")
      (fields
        (field (name "04_MANUFACTURER PART NUMBER") "RT0603FRE13100RL")
        (field (name "05_DIGIKEY PART NUMBER") "13-RT0603FRE13100RLCT-ND")
        (field (name "TOLERANCIA") "1%")
      )
      (libsource (lib "Libreria_Altium") (part "Resistor"))
    )
    (comp (ref "R13")
      (value "100R")
      (footprint "RES_SMD_0603")
      (description "100 Ohms ±1% 0.1W, 1/10W Chip Resistor 0603 (1608 Metric) Thin Film")
      (fields
        (field (name "04_MANUFACTURER PART NUMBER") "RT0603FRE13100RL")
        (field (name "05_DIGIKEY PART NUMBER") "13-RT0603FRE13100RLCT-ND")
        (field (name "TOLERANCIA") "1%")
      )
      (libsource (lib "Libreria_Altium") (part "Resistor"))
    )
    (comp (ref "R14")
      (value "10K")
      (footprint "RES_SMD_0603")
      (description "10 kOhms ±1% 0.1W, 1/10W Chip Resistor 0603 (1608 Metric) Thin Film")
      (fields
        (field (name "04_MANUFACTURER PART NUMBER") "RT0603FRE0710KL")
        (field (name "05_DIGIKEY PART NUMBER") "YAG2321CT-ND")
        (field (name "TOLERANCIA") "1%")
      )
      (libsource (lib "Libreria_Altium") (part "Resistor"))
    )
    (comp (ref "R15")
      (value "3K9")
      (footprint "RES_SMD_0603")
      (description "3.9 kOhms ±1% 0.1W, 1/10W Chip Resistor 0603 (1608 Metric) Thick Film")
      (fields
        (field (name "04_MANUFACTURER PART NUMBER") "RC0603FR-133K9L")
        (field (name "05_DIGIKEY PART NUMBER") "13-RC0603FR-133K9LCT-ND")
        (field (name "TOLERANCIA") "1%")
      )
      (libsource (lib "Libreria_Altium") (part "Resistor"))
    )
    (comp (ref "R16")
      (value "680R")
      (footprint "RES_SMD_0603")
      (description "680 Ohms ±1% 0.1W, 1/10W Chip Resistor 0603 (1608 Metric) Moisture Resistant Thick Film")
      (fields
        (field (name "04_MANUFACTURER PART NUMBER") "RC0603FR-07680RL")
        (field (name "05_DIGIKEY PART NUMBER") "311-680HRCT-ND")
        (field (name "TOLERANCIA") "1%")
      )
      (libsource (lib "Libreria_Altium") (part "Resistor"))
    )
    (comp (ref "R17")
      (value "3R9")
      (footprint "RES_SMD_0603")
      (fields
        (field (name "04_MANUFACTURER PART NUMBER") "RT0603FRE073R9L")
        (field (name "05_DIGIKEY PART NUMBER") "13-RT0603FRE073R9LCT-ND")
        (field (name "TOLERANCIA") "1%")
      )
      (libsource (lib "Libreria_Altium") (part "Resistor"))
    )
    (comp (ref "R18")
      (value "1K")
      (footprint "RES_SMD_0603")
      (description "1 kOhms ±1% 0.1W, 1/10W Chip Resistor 0603 (1608 Metric) Thin Film")
      (fields
        (field (name "04_MANUFACTURER PART NUMBER") "RT0603FRE131KL")
        (field (name "05_DIGIKEY PART NUMBER") "13-RT0603FRE131KLCT-ND")
        (field (name "TOLERANCIA") "1%")
      )
      (libsource (lib "Libreria_Altium") (part "Resistor"))
    )
    (comp (ref "R19")
      (value "1K")
      (footprint "RES_SMD_0603")
      (description "1 kOhms ±1% 0.1W, 1/10W Chip Resistor 0603 (1608 Metric) Thin Film")
      (fields
        (field (name "04_MANUFACTURER PART NUMBER") "RT0603FRE131KL")
        (field (name "05_DIGIKEY PART NUMBER") "13-RT0603FRE131KLCT-ND")
        (field (name "TOLERANCIA") "1%")
      )
      (libsource (lib "Libreria_Altium") (part "Resistor"))
    )
    (comp (ref "R20")
      (value "1K")
      (footprint "RES_SMD_0603")
      (description "1 kOhms ±1% 0.1W, 1/10W Chip Resistor 0603 (1608 Metric) Thin Film")
      (fields
        (field (name "04_MANUFACTURER PART NUMBER") "RT0603FRE131KL")
        (field (name "05_DIGIKEY PART NUMBER") "13-RT0603FRE131KLCT-ND")
        (field (name "TOLERANCIA") "1%")
      )
      (libsource (lib "Libreria_Altium") (part "Resistor"))
    )
    (comp (ref "R21")
      (value "1K")
      (footprint "RES_SMD_0603")
      (description "1 kOhms ±1% 0.1W, 1/10W Chip Resistor 0603 (1608 Metric) Thin Film")
      (fields
        (field (name "04_MANUFACTURER PART NUMBER") "RT0603FRE131KL")
        (field (name "05_DIGIKEY PART NUMBER") "13-RT0603FRE131KLCT-ND")
        (field (name "TOLERANCIA") "1%")
      )
      (libsource (lib "Libreria_Altium") (part "Resistor"))
    )
    (comp (ref "R22")
      (value "1K")
      (footprint "RES_SMD_0603")
      (description "1 kOhms ±1% 0.1W, 1/10W Chip Resistor 0603 (1608 Metric) Thin Film")
      (fields
        (field (name "04_MANUFACTURER PART NUMBER") "RT0603FRE131KL")
        (field (name "05_DIGIKEY PART NUMBER") "13-RT0603FRE131KLCT-ND")
        (field (name "TOLERANCIA") "1%")
      )
      (libsource (lib "Libreria_Altium") (part "Resistor"))
    )
    (comp (ref "R23")
      (value "1K")
      (footprint "RES_SMD_0603")
      (description "1 kOhms ±1% 0.1W, 1/10W Chip Resistor 0603 (1608 Metric) Thin Film")
      (fields
        (field (name "04_MANUFACTURER PART NUMBER") "RT0603FRE131KL")
        (field (name "05_DIGIKEY PART NUMBER") "13-RT0603FRE131KLCT-ND")
        (field (name "TOLERANCIA") "1%")
      )
      (libsource (lib "Libreria_Altium") (part "Resistor"))
    )
    (comp (ref "R24")
      (value "1K")
      (footprint "RES_SMD_0603")
      (description "1 kOhms ±1% 0.1W, 1/10W Chip Resistor 0603 (1608 Metric) Thin Film")
      (fields
        (field (name "04_MANUFACTURER PART NUMBER") "RT0603FRE131KL")
        (field (name "05_DIGIKEY PART NUMBER") "13-RT0603FRE131KLCT-ND")
        (field (name "TOLERANCIA") "1%")
      )
      (libsource (lib "Libreria_Altium") (part "Resistor"))
    )
    (comp (ref "R25")
      (value "3R9")
      (footprint "RES_SMD_0603")
      (fields
        (field (name "04_MANUFACTURER PART NUMBER") "RT0603FRE073R9L")
        (field (name "05_DIGIKEY PART NUMBER") "13-RT0603FRE073R9LCT-ND")
        (field (name "TOLERANCIA") "1%")
      )
      (libsource (lib "Libreria_Altium") (part "Resistor"))
    )
    (comp (ref "R26")
      (value "1K")
      (footprint "RES_SMD_0603")
      (description "1 kOhms ±1% 0.1W, 1/10W Chip Resistor 0603 (1608 Metric) Thin Film")
      (fields
        (field (name "04_MANUFACTURER PART NUMBER") "RT0603FRE131KL")
        (field (name "05_DIGIKEY PART NUMBER") "13-RT0603FRE131KLCT-ND")
        (field (name "TOLERANCIA") "1%")
      )
      (libsource (lib "Libreria_Altium") (part "Resistor"))
    )
    (comp (ref "R27")
      (value "1K")
      (footprint "RES_SMD_0603")
      (description "1 kOhms ±1% 0.1W, 1/10W Chip Resistor 0603 (1608 Metric) Thin Film")
      (fields
        (field (name "04_MANUFACTURER PART NUMBER") "RT0603FRE131KL")
        (field (name "05_DIGIKEY PART NUMBER") "13-RT0603FRE131KLCT-ND")
        (field (name "TOLERANCIA") "1%")
      )
      (libsource (lib "Libreria_Altium") (part "Resistor"))
    )
    (comp (ref "RA_1")
      (value "1K")
      (footprint "RES_SMD_0603")
      (description "1 kOhms ±1% 0.1W, 1/10W Chip Resistor 0603 (1608 Metric) Thin Film")
      (fields
        (field (name "04_MANUFACTURER PART NUMBER") "RT0603FRE131KL")
        (field (name "05_DIGIKEY PART NUMBER") "13-RT0603FRE131KLCT-ND")
        (field (name "TOLERANCIA") "1%")
      )
      (libsource (lib "Libreria_Altium") (part "Resistor"))
    )
    (comp (ref "RA_2")
      (value "49R9")
      (footprint "RES_SMD_0603")
      (description "49.9 Ohms ±1% 0.1W, 1/10W Chip Resistor 0603 (1608 Metric) Thin Film")
      (fields
        (field (name "04_MANUFACTURER PART NUMBER") "RT0603FRD0749R9L")
        (field (name "05_DIGIKEY PART NUMBER") "13-RT0603FRD0749R9LCT-ND")
        (field (name "TOLERANCIA") "1%")
      )
      (libsource (lib "Libreria_Altium") (part "Resistor"))
    )
    (comp (ref "RA_3")
      (value "100R")
      (footprint "RES_SMD_0603")
      (description "100 Ohms ±1% 0.1W, 1/10W Chip Resistor 0603 (1608 Metric) Thin Film")
      (fields
        (field (name "04_MANUFACTURER PART NUMBER") "RT0603FRE13100RL")
        (field (name "05_DIGIKEY PART NUMBER") "13-RT0603FRE13100RLCT-ND")
        (field (name "TOLERANCIA") "1%")
      )
      (libsource (lib "Libreria_Altium") (part "Resistor"))
    )
    (comp (ref "RA_4")
      (value "1M")
      (footprint "RES_SMD_0603")
      (description "499 kOhms ±1% 0.1W, 1/10W Chip Resistor 0603 (1608 Metric) Thin Film")
      (fields
        (field (name "04_MANUFACTURER PART NUMBER") "RT0603BRD071ML")
        (field (name "05_DIGIKEY PART NUMBER") "YAG4498CT-ND")
        (field (name "TOLERANCIA") "0.1%")
      )
      (libsource (lib "Libreria_Altium") (part "Resistor"))
    )
    (comp (ref "RB_1")
      (value "1M")
      (footprint "RES_SMD_0603")
      (description "499 kOhms ±1% 0.1W, 1/10W Chip Resistor 0603 (1608 Metric) Thin Film")
      (fields
        (field (name "04_MANUFACTURER PART NUMBER") "RT0603BRD071ML")
        (field (name "05_DIGIKEY PART NUMBER") "YAG4498CT-ND")
        (field (name "TOLERANCIA") "0.1%")
      )
      (libsource (lib "Libreria_Altium") (part "Resistor"))
    )
    (comp (ref "RB_2")
      (value "100R")
      (footprint "RES_SMD_0603")
      (description "100 Ohms ±1% 0.1W, 1/10W Chip Resistor 0603 (1608 Metric) Thin Film")
      (fields
        (field (name "04_MANUFACTURER PART NUMBER") "RT0603FRE13100RL")
        (field (name "05_DIGIKEY PART NUMBER") "13-RT0603FRE13100RLCT-ND")
        (field (name "TOLERANCIA") "1%")
      )
      (libsource (lib "Libreria_Altium") (part "Resistor"))
    )
    (comp (ref "RB_3")
      (value "49R9")
      (footprint "RES_SMD_0603")
      (description "49.9 Ohms ±1% 0.1W, 1/10W Chip Resistor 0603 (1608 Metric) Thin Film")
      (fields
        (field (name "04_MANUFACTURER PART NUMBER") "RT0603FRD0749R9L")
        (field (name "05_DIGIKEY PART NUMBER") "13-RT0603FRD0749R9LCT-ND")
        (field (name "TOLERANCIA") "1%")
      )
      (libsource (lib "Libreria_Altium") (part "Resistor"))
    )
    (comp (ref "RB_4")
      (value "1K")
      (footprint "RES_SMD_0603")
      (description "1 kOhms ±1% 0.1W, 1/10W Chip Resistor 0603 (1608 Metric) Thin Film")
      (fields
        (field (name "04_MANUFACTURER PART NUMBER") "RT0603FRE131KL")
        (field (name "05_DIGIKEY PART NUMBER") "13-RT0603FRE131KLCT-ND")
        (field (name "TOLERANCIA") "1%")
      )
      (libsource (lib "Libreria_Altium") (part "Resistor"))
    )
    (comp (ref "RG1")
      (value "100R")
      (footprint "RES_SMD_0603")
      (description "100 Ohms ±1% 0.1W, 1/10W Chip Resistor 0603 (1608 Metric) Thin Film")
      (fields
        (field (name "04_MANUFACTURER PART NUMBER") "RT0603FRE13100RL")
        (field (name "05_DIGIKEY PART NUMBER") "13-RT0603FRE13100RLCT-ND")
        (field (name "TOLERANCIA") "1%")
      )
      (libsource (lib "Libreria_Altium") (part "Resistor"))
    )
    (comp (ref "RG2")
      (value "1K")
      (footprint "RES_SMD_0603")
      (description "1 kOhms ±1% 0.1W, 1/10W Chip Resistor 0603 (1608 Metric) Thin Film")
      (fields
        (field (name "04_MANUFACTURER PART NUMBER") "RT0603FRE131KL")
        (field (name "05_DIGIKEY PART NUMBER") "13-RT0603FRE131KLCT-ND")
        (field (name "TOLERANCIA") "1%")
      )
      (libsource (lib "Libreria_Altium") (part "Resistor"))
    )
    (comp (ref "RG3")
      (value "DNP")
      (footprint "RES_SMD_0603")
      (description "100 Ohms ±1% 0.1W, 1/10W Chip Resistor 0603 (1608 Metric) Thin Film")
      (fields
        (field (name "04_MANUFACTURER PART NUMBER") "RT0603FRE13100RL")
        (field (name "05_DIGIKEY PART NUMBER") "13-RT0603FRE13100RLCT-ND")
        (field (name "TOLERANCIA") "1%")
      )
      (libsource (lib "Libreria_Altium") (part "Resistor"))
    )
    (comp (ref "RG4")
      (value "5K48")
      (footprint "RES_SMD_0603")
      (description "5.49 kOhms ±0.1% 0.1W, 1/10W Chip Resistor 0603 (1608 Metric) Thin Film")
      (fields
        (field (name "04_MANUFACTURER PART NUMBER") "RT0603BRD075K49L")
        (field (name "05_DIGIKEY PART NUMBER") "YAG1698CT-ND")
        (field (name "TOLERANCIA") "0.1%")
      )
      (libsource (lib "Libreria_Altium") (part "Resistor"))
    )
    (comp (ref "RPB_1")
      (value "866R")
      (footprint "RES_SMD_0603")
      (description "866 Ohms ±1% 0.1W, 1/10W Chip Resistor 0603 (1608 Metric) Thin Film")
      (fields
        (field (name "04_MANUFACTURER PART NUMBER") "RT0603FRE07866RL")
        (field (name "05_DIGIKEY PART NUMBER") "13-RT0603FRE07866RLCT-ND")
        (field (name "TOLERANCIA") "1%")
      )
      (libsource (lib "Libreria_Altium") (part "Resistor"))
    )
    (comp (ref "RPB_2")
      (value "49R9")
      (footprint "RES_SMD_0603")
      (description "49.9 Ohms ±1% 0.1W, 1/10W Chip Resistor 0603 (1608 Metric) Thin Film")
      (fields
        (field (name "04_MANUFACTURER PART NUMBER") "RT0603FRD0749R9L")
        (field (name "05_DIGIKEY PART NUMBER") "13-RT0603FRD0749R9LCT-ND")
        (field (name "TOLERANCIA") "1%")
      )
      (libsource (lib "Libreria_Altium") (part "Resistor"))
    )
    (comp (ref "RPB_3")
      (value "10K")
      (footprint "RES_SMD_0603")
      (description "10 kOhms ±1% 0.1W, 1/10W Chip Resistor 0603 (1608 Metric) Thin Film")
      (fields
        (field (name "04_MANUFACTURER PART NUMBER") "RT0603FRE0710KL")
        (field (name "05_DIGIKEY PART NUMBER") "YAG2321CT-ND")
        (field (name "TOLERANCIA") "1%")
      )
      (libsource (lib "Libreria_Altium") (part "Resistor"))
    )
    (comp (ref "SW1")
      (value "Coupling")
      (footprint "MFS201N-9-Z")
      (description "Slide Switch SPDT  90° Through Hole")
      (fields
        (field (name "04_MANUFACTURER PART NUMBER") "MFS201N-9-Z")
        (field (name "05_DIGIKEY PART NUMBER") "563-1565-ND")
      )
      (libsource (lib "Libreria_Altium") (part "Interruptor DPDT"))
    )
    (comp (ref "SW2")
      (value "MODE")
      (footprint "HASS0399")
      (description "SWITCH SLIDE DP4T 300MA 30V")
      (fields
        (field (name "04_MANUFACTURER PART NUMBER") "HASS0399")
        (field (name "05_DIGIKEY PART NUMBER") "CKN10394-ND")
      )
      (libsource (lib "Libreria_Altium") (part "Interruptor 2P4T"))
    )
    (comp (ref "SW3")
      (value "GAIN")
      (footprint "OS103012MU1QP1")
      (description "Slide Switch SP3T Through Hole")
      (fields
        (field (name "04_MANUFACTURER PART NUMBER") "OS103012MU1QP1")
        (field (name "05_DIGIKEY PART NUMBER") "CKN9552-ND")
      )
      (libsource (lib "Libreria_Altium") (part "Interruptor SP3T"))
    )
    (comp (ref "SW4")
      (value "10X")
      (footprint "MFS201N-9-Z")
      (description "Slide Switch SPDT  90° Through Hole")
      (fields
        (field (name "04_MANUFACTURER PART NUMBER") "MFS201N-9-Z")
        (field (name "05_DIGIKEY PART NUMBER") "563-1565-ND")
      )
      (libsource (lib "Libreria_Altium") (part "Interruptor DPDT"))
    )
    (comp (ref "SW5")
      (value "Bandwith")
      (footprint "HASS0399")
      (description "SWITCH SLIDE DP4T 300MA 30V")
      (fields
        (field (name "04_MANUFACTURER PART NUMBER") "HASS0399")
        (field (name "05_DIGIKEY PART NUMBER") "CKN10394-ND")
      )
      (libsource (lib "Libreria_Altium") (part "Interruptor 2P4T"))
    )
    (comp (ref "SW6")
      (value "OFFSET")
      (footprint "MFS201N-9-Z")
      (description "Slide Switch SPDT  90° Through Hole")
      (fields
        (field (name "04_MANUFACTURER PART NUMBER") "MFS201N-9-Z")
        (field (name "05_DIGIKEY PART NUMBER") "563-1565-ND")
      )
      (libsource (lib "Libreria_Altium") (part "Interruptor DPDT"))
    )
    (comp (ref "SW7")
      (value "ON/OFF")
      (footprint "MFS201N-9-Z")
      (description "Slide Switch SPDT  90° Through Hole")
      (fields
        (field (name "04_MANUFACTURER PART NUMBER") "MFS201N-9-Z")
        (field (name "05_DIGIKEY PART NUMBER") "563-1565-ND")
      )
      (libsource (lib "Libreria_Altium") (part "Interruptor DPDT"))
    )
    (comp (ref "TP1")
      (value "AUX")
      (footprint "Test_Point_THT")
      (description "Testpoint")
      (fields (field (name "04_MANUFACTURER PART NUMBER") "NA"))
      (libsource (lib "Libreria_Altium") (part "TestPoint_SMD"))
    )
    (comp (ref "TP2")
      (value "UGND")
      (footprint "Test_Point_THT")
      (description "Testpoint")
      (fields (field (name "04_MANUFACTURER PART NUMBER") "NA"))
      (libsource (lib "Libreria_Altium") (part "TestPoint_SMD"))
    )
    (comp (ref "TP3")
      (value "AUX_GND")
      (footprint "Test_Point_THT")
      (description "Testpoint")
      (fields (field (name "04_MANUFACTURER PART NUMBER") "NA"))
      (libsource (lib "Libreria_Altium") (part "TestPoint_SMD"))
    )
    (comp (ref "TP4")
      (value "+V")
      (footprint "Test_Point_THT")
      (description "Testpoint")
      (fields (field (name "04_MANUFACTURER PART NUMBER") "NA"))
      (libsource (lib "Libreria_Altium") (part "TestPoint_SMD"))
    )
    (comp (ref "TP5")
      (value "+5Vref")
      (footprint "Test_Point_THT")
      (description "Testpoint")
      (fields (field (name "04_MANUFACTURER PART NUMBER") "NA"))
      (libsource (lib "Libreria_Altium") (part "TestPoint_SMD"))
    )
    (comp (ref "TP6")
      (value "USB")
      (footprint "Test_Point_THT")
      (description "Testpoint")
      (fields (field (name "04_MANUFACTURER PART NUMBER") "NA"))
      (libsource (lib "Libreria_Altium") (part "TestPoint_SMD"))
    )
    (comp (ref "TP7")
      (value "Vsum")
      (footprint "Test_Point_THT")
      (description "Testpoint")
      (fields (field (name "04_MANUFACTURER PART NUMBER") "NA"))
      (libsource (lib "Libreria_Altium") (part "TestPoint_SMD"))
    )
    (comp (ref "TP8")
      (value "Vcc")
      (footprint "Test_Point_THT")
      (description "Testpoint")
      (fields (field (name "04_MANUFACTURER PART NUMBER") "NA"))
      (libsource (lib "Libreria_Altium") (part "TestPoint_SMD"))
    )
    (comp (ref "TP9")
      (value "GND")
      (footprint "Test_Point_THT")
      (description "Testpoint")
      (fields (field (name "04_MANUFACTURER PART NUMBER") "NA"))
      (libsource (lib "Libreria_Altium") (part "TestPoint_SMD"))
    )
    (comp (ref "TP10")
      (value "PGND")
      (footprint "Test_Point_THT")
      (description "Testpoint")
      (fields (field (name "04_MANUFACTURER PART NUMBER") "NA"))
      (libsource (lib "Libreria_Altium") (part "TestPoint_SMD"))
    )
    (comp (ref "TP11")
      (value "Vee")
      (footprint "Test_Point_THT")
      (description "Testpoint")
      (fields (field (name "04_MANUFACTURER PART NUMBER") "NA"))
      (libsource (lib "Libreria_Altium") (part "TestPoint_SMD"))
    )
    (comp (ref "TP12")
      (value "-5Vref")
      (footprint "Test_Point_THT")
      (description "Testpoint")
      (fields (field (name "04_MANUFACTURER PART NUMBER") "NA"))
      (libsource (lib "Libreria_Altium") (part "TestPoint_SMD"))
    )
    (comp (ref "TP13")
      (value "-V")
      (footprint "Test_Point_THT")
      (description "Testpoint")
      (fields (field (name "04_MANUFACTURER PART NUMBER") "NA"))
      (libsource (lib "Libreria_Altium") (part "TestPoint_SMD"))
    )
    (comp (ref "TR1")
      (value "200K")
      (footprint "Trimpot J-Lead")
      (description "1 kOhms 0.25W, 1/4W J Lead Surface Mount Trimmer Potentiometer Cermet 11.0 Turn Top Adjustment")
      (fields
        (field (name "04_MANUFACTURER PART NUMBER") "PVG5A204C03R00")
        (field (name "05_DIGIKEY PART NUMBER") "490-2668-1-ND")
        (field (name "TOLERANCIA") "10%")
      )
      (libsource (lib "Libreria_Altium") (part "Trimpot"))
    )
    (comp (ref "TR2")
      (value "10K")
      (footprint "POTENCIOMETRO_RK09K1130081")
      (description "10k Ohm 1 Gang Linear Through Hole Potentiometer 1.0 Turns Carbon 0.08W PC Pins, Board Locks")
      (fields
        (field (name "04_MANUFACTURER PART NUMBER") "RK09K1130081")
        (field (name "05_DIGIKEY PART NUMBER") "4809-RK09K1130081-ND")
      )
      (libsource (lib "Libreria_Altium") (part "Trimpot"))
    )
    (comp (ref "TR3")
      (value "100R")
      (footprint "Trimpot J-Lead")
      (description "100 Ohms 0.25W, 1/4W J Lead Surface Mount Trimmer Potentiometer Cermet 11.0 Turn Top Adjustment")
      (fields
        (field (name "04_MANUFACTURER PART NUMBER") "PVG5A101C03R00")
        (field (name "05_DIGIKEY PART NUMBER") "490-2659-1-ND")
      )
      (libsource (lib "Libreria_Altium") (part "Trimpot"))
    )
    (comp (ref "U1")
      (value "ADA4610-1ARZ-R7")
      (footprint "SOIC-8_IPC")
      (description "J-FET Amplifier 1 Circuit Rail-to-Rail 8-SOIC")
      (fields (field (name "05_DIGIKEY PART NUMBER") "505-ADA4610-1ARZ-R7CT-ND"))
      (libsource (lib "Libreria_Altium") (part "Amplificador Operacional"))
    )
    (comp (ref "U2")
      (value "INA826AIDR")
      (footprint "SOIC-8_IPC")
      (description "Instrumentation Amplifier 1 Circuit Rail-to-Rail 8-SOIC")
      (fields (field (name "05_DIGIKEY PART NUMBER") "296-30238-1-ND"))
      (libsource (lib "Libreria_Altium") (part "INA826AIDR"))
    )
    (comp (ref "U3")
      (value "ADA4610-1ARZ-R7")
      (footprint "SOIC-8_IPC")
      (description "J-FET Amplifier 1 Circuit Rail-to-Rail 8-SOIC")
      (fields (field (name "05_DIGIKEY PART NUMBER") "505-ADA4610-1ARZ-R7CT-ND"))
      (libsource (lib "Libreria_Altium") (part "Amplificador Operacional"))
    )
    (comp (ref "U4")
      (value "BD9G101G-TR")
      (footprint "SOT_23-6")
      (description "Buck Switching Regulator IC Positive Adjustable 1V 1 Output 500mA SOT-23-6")
      (fields (field (name "05_DIGIKEY PART NUMBER") "BD9G101G-CT-ND"))
      (libsource (lib "Libreria_Altium") (part "BD9G101G-TR"))
    )
    (comp (ref "U5")
      (value "TPS7B92120DBVR")
      (footprint "SOT_23-5")
      (description "Linear Voltage Regulator IC Positive Fixed 1 Output 300mA SOT-23-5")
      (fields (field (name "05_DIGIKEY PART NUMBER") "296-TPS7B92120DBVRCT-ND"))
      (libsource (lib "Libreria_Altium") (part "TPS7B92120DBVR"))
    )
    (comp (ref "U6")
      (value "DETN02L-15N")
      (footprint "DETN02-N")
      (description "Isolated Module DC DC Converter 2 Output 15V -15V 66mA, 66mA 4.5V - 5.5V Input")
      (fields (field (name "05_DIGIKEY PART NUMBER") "1866-DETN02L-15N-ND"))
      (libsource (lib "Libreria_Altium") (part "DETN02-N"))
    )
    (comp (ref "U7")
      (value "TL431BIDBZR")
      (footprint "SOT_23-3")
      (description "Shunt Voltage Reference IC Adjustable 2.495V 36 VV ±0.5% 100 mA SOT-23-3")
      (fields (field (name "05_DIGIKEY PART NUMBER") "296-18872-1-ND"))
      (libsource (lib "Libreria_Altium") (part "TL431"))
    )
    (comp (ref "U8")
      (value "TL431BIDBZR")
      (footprint "SOT_23-3")
      (description "Shunt Voltage Reference IC Adjustable 2.495V 36 VV ±0.5% 100 mA SOT-23-3")
      (fields (field (name "05_DIGIKEY PART NUMBER") "296-18872-1-ND"))
      (libsource (lib "Libreria_Altium") (part "TL431"))
    )
    (comp (ref "U9")
      (value "XC6901DC01MR")
      (footprint "SOT_25")
      (description "Linear Voltage Regulator IC Negative Fixed 1 Output 200mA SOT-25")
      (fields
        (field (name "04_MANUFACTURER PART NUMBER") "XC6901DC01MR-G")
        (field (name "05_DIGIKEY PART NUMBER") "893-XC6901DC01MR-GCT-ND")
      )
      (libsource (lib "Libreria_Altium") (part "XC6901DC01MR-G"))
    )
  )
  (nets
    (net (code "1") (name "+5Vref") (class "Default")
      (node (ref "C31") (pin "2") (pinfunction "2_2") (pintype "passive"))
      (node (ref "R11") (pin "1") (pinfunction "1_1") (pintype "passive"))
      (node (ref "R19") (pin "2") (pinfunction "2_2") (pintype "passive"))
      (node (ref "R20") (pin "2") (pinfunction "2_2") (pintype "passive"))
      (node (ref "R6") (pin "1") (pinfunction "1_1") (pintype "passive"))
      (node (ref "TP5") (pin "1") (pinfunction "1_1") (pintype "passive"))
      (node (ref "U7") (pin "1") (pinfunction "1_1") (pintype "passive"))
    )
    (net (code "2") (name "-5Vref") (class "Default")
      (node (ref "C43") (pin "1") (pinfunction "1_1") (pintype "passive"))
      (node (ref "R10") (pin "2") (pinfunction "2_2") (pintype "passive"))
      (node (ref "R14") (pin "1") (pinfunction "1_1") (pintype "passive"))
      (node (ref "R24") (pin "1") (pinfunction "1_1") (pintype "passive"))
      (node (ref "R27") (pin "2") (pinfunction "2_2") (pintype "passive"))
      (node (ref "TP12") (pin "1") (pinfunction "1_1") (pintype "passive"))
      (node (ref "U8") (pin "3") (pinfunction "3_3") (pintype "passive"))
    )
    (net (code "3") (name "/BIAS_TRIMM") (class "Default")
      (node (ref "SW6") (pin "6") (pinfunction "NO2_6") (pintype "passive"))
      (node (ref "TR3") (pin "3") (pinfunction "3_3") (pintype "passive"))
    )
    (net (code "4") (name "/IN+") (class "Default")
      (node (ref "CONN1") (pin "1") (pinfunction "SIGNAL_1") (pintype "passive"))
      (node (ref "RA_2") (pin "1") (pinfunction "1_1") (pintype "passive"))
    )
    (net (code "5") (name "/IN-") (class "Default")
      (node (ref "CONN3") (pin "1") (pinfunction "SIGNAL_1") (pintype "passive"))
      (node (ref "RB_3") (pin "1") (pinfunction "1_1") (pintype "passive"))
    )
    (net (code "6") (name "/IN_A") (class "Default")
      (node (ref "CA_2") (pin "2") (pinfunction "2_2") (pintype "passive"))
      (node (ref "RA_4") (pin "2") (pinfunction "2_2") (pintype "passive"))
      (node (ref "SW1") (pin "1") (pinfunction "NC1_1") (pintype "passive"))
      (node (ref "SW2") (pin "10") (pinfunction "NO8_10") (pintype "passive"))
      (node (ref "SW2") (pin "2") (pinfunction "NC2_2") (pintype "passive"))
      (node (ref "SW2") (pin "9") (pinfunction "NO7_9") (pintype "passive"))
    )
    (net (code "7") (name "/IN_B") (class "Default")
      (node (ref "CB_1") (pin "2") (pinfunction "2_2") (pintype "passive"))
      (node (ref "RB_1") (pin "1") (pinfunction "1_1") (pintype "passive"))
      (node (ref "SW1") (pin "4") (pinfunction "NC2_4") (pintype "passive"))
      (node (ref "SW2") (pin "5") (pinfunction "NO3_5") (pintype "passive"))
      (node (ref "SW2") (pin "7") (pinfunction "NO5_7") (pintype "passive"))
      (node (ref "SW2") (pin "8") (pinfunction "NO6_8") (pintype "passive"))
    )
    (net (code "8") (name "/OFFSET_OUT") (class "Default")
      (node (ref "SW6") (pin "4") (pinfunction "NC2_4") (pintype "passive"))
      (node (ref "TR2") (pin "3") (pinfunction "3_3") (pintype "passive"))
    )
    (net (code "9") (name "/OFFSET_REFERENCE") (class "Default")
      (node (ref "C16") (pin "2") (pinfunction "2_2") (pintype "passive"))
      (node (ref "R8") (pin "1") (pinfunction "1_1") (pintype "passive"))
      (node (ref "R9") (pin "2") (pinfunction "2_2") (pintype "passive"))
      (node (ref "U2") (pin "6") (pinfunction "Ref_6") (pintype "passive"))
    )
    (net (code "10") (name "/OUT") (class "Default")
      (node (ref "CONN2") (pin "1") (pinfunction "1_1") (pintype "passive"))
      (node (ref "R5") (pin "2") (pinfunction "2_2") (pintype "passive"))
    )
    (net (code "11") (name "AUX") (class "Default")
      (node (ref "C27") (pin "2") (pinfunction "2_2") (pintype "passive"))
      (node (ref "C28") (pin "2") (pinfunction "2_2") (pintype "passive"))
      (node (ref "D3") (pin "K") (pinfunction "K_K") (pintype "passive"))
      (node (ref "F2") (pin "1") (pinfunction "1_1") (pintype "passive"))
      (node (ref "Q1") (pin "1") (pinfunction "G_1") (pintype "passive"))
      (node (ref "TP1") (pin "1") (pinfunction "1_1") (pintype "passive"))
      (node (ref "U4") (pin "4") (pinfunction "EN_4") (pintype "passive"))
      (node (ref "U4") (pin "5") (pinfunction "Vcc_5") (pintype "passive"))
    )
    (net (code "12") (name "AUX_GND") (class "Default")
      (node (ref "C27") (pin "1") (pinfunction "1_1") (pintype "passive"))
      (node (ref "CONN5") (pin "2") (pinfunction "2_2") (pintype "passive"))
      (node (ref "D3") (pin "A") (pinfunction "A_A") (pintype "passive"))
      (node (ref "Q1") (pin "3") (pinfunction "D_3") (pintype "passive"))
      (node (ref "TP2") (pin "1") (pinfunction "1_1") (pintype "passive"))
      (node (ref "TP3") (pin "1") (pinfunction "1_1") (pintype "passive"))
    )
    (net (code "13") (name "GND") (class "Default")
      (node (ref "C1") (pin "1") (pinfunction "1_1") (pintype "passive"))
      (node (ref "C10") (pin "1") (pinfunction "1_1") (pintype "passive"))
      (node (ref "C11") (pin "1") (pinfunction "1_1") (pintype "passive"))
      (node (ref "C12") (pin "1") (pinfunction "1_1") (pintype "passive"))
      (node (ref "C13") (pin "1") (pinfunction "1_1") (pintype "passive"))
      (node (ref "C14") (pin "1") (pinfunction "1_1") (pintype "passive"))
      (node (ref "C15") (pin "1") (pinfunction "1_1") (pintype "passive"))
      (node (ref "C17") (pin "1") (pinfunction "1_1") (pintype "passive"))
      (node (ref "C18") (pin "1") (pinfunction "1_1") (pintype "passive"))
      (node (ref "C19") (pin "2") (pinfunction "2_2") (pintype "passive"))
      (node (ref "C20") (pin "1") (pinfunction "1_1") (pintype "passive"))
      (node (ref "C21") (pin "1") (pinfunction "1_1") (pintype "passive"))
      (node (ref "C22") (pin "1") (pinfunction "1_1") (pintype "passive"))
      (node (ref "C24") (pin "2") (pinfunction "2_2") (pintype "passive"))
      (node (ref "C3") (pin "1") (pinfunction "1_1") (pintype "passive"))
      (node (ref "C30") (pin "1") (pinfunction "1_1") (pintype "passive"))
      (node (ref "C31") (pin "1") (pinfunction "1_1") (pintype "passive"))
      (node (ref "C33") (pin "1") (pinfunction "1_1") (pintype "passive"))
      (node (ref "C34") (pin "1") (pinfunction "1_1") (pintype "passive"))
      (node (ref "C35") (pin "1") (pinfunction "1_1") (pintype "passive"))
      (node (ref "C36") (pin "1") (pinfunction "1_1") (pintype "passive"))
      (node (ref "C39") (pin "2") (pinfunction "2_2") (pintype "passive"))
      (node (ref "C4") (pin "1") (pinfunction "1_1") (pintype "passive"))
      (node (ref "C40") (pin "2") (pinfunction "2_2") (pintype "passive"))
      (node (ref "C41") (pin "2") (pinfunction "2_2") (pintype "passive"))
      (node (ref "C42") (pin "2") (pinfunction "2_2") (pintype "passive"))
      (node (ref "C43") (pin "2") (pinfunction "2_2") (pintype "passive"))
      (node (ref "C5") (pin "1") (pinfunction "1_1") (pintype "passive"))
      (node (ref "C6") (pin "1") (pinfunction "1_1") (pintype "passive"))
      (node (ref "C7") (pin "1") (pinfunction "1_1") (pintype "passive"))
      (node (ref "C8") (pin "1") (pinfunction "1_1") (pintype "passive"))
      (node (ref "C9") (pin "1") (pinfunction "1_1") (pintype "passive"))
      (node (ref "CA_1") (pin "2") (pinfunction "2_2") (pintype "passive"))
      (node (ref "CB_2") (pin "1") (pinfunction "1_1") (pintype "passive"))
      (node (ref "CONN1") (pin "2") (pinfunction "2_2") (pintype "passive"))
      (node (ref "CONN2") (pin "2") (pinfunction "2_2") (pintype "passive"))
      (node (ref "CONN3") (pin "2") (pinfunction "2_2") (pintype "passive"))
      (node (ref "D6") (pin "K") (pinfunction "K_K") (pintype "passive"))
      (node (ref "DA_1") (pin "A") (pinfunction "A_A") (pintype "passive"))
      (node (ref "DB_1") (pin "K") (pinfunction "K_K") (pintype "passive"))
      (node (ref "R12") (pin "2") (pinfunction "2_2") (pintype "passive"))
      (node (ref "R13") (pin "1") (pinfunction "1_1") (pintype "passive"))
      (node (ref "R22") (pin "1") (pinfunction "1_1") (pintype "passive"))
      (node (ref "R23") (pin "2") (pinfunction "2_2") (pintype "passive"))
      (node (ref "R7") (pin "2") (pinfunction "2_2") (pintype "passive"))
      (node (ref "SW2") (pin "3") (pinfunction "NO1_3") (pintype "passive"))
      (node (ref "SW2") (pin "4") (pinfunction "NO2_4") (pintype "passive"))
      (node (ref "SW3") (pin "2") (pinfunction "COM1_2") (pintype "passive"))
      (node (ref "TP9") (pin "1") (pinfunction "1_1") (pintype "passive"))
      (node (ref "TR1") (pin "3") (pinfunction "3_3") (pintype "passive"))
      (node (ref "U5") (pin "2") (pinfunction "GND_2") (pintype "passive"))
      (node (ref "U6") (pin "5") (pinfunction "Comm_5") (pintype "passive"))
      (node (ref "U7") (pin "3") (pinfunction "3_3") (pintype "passive"))
      (node (ref "U8") (pin "1") (pinfunction "1_1") (pintype "passive"))
      (node (ref "U9") (pin "1") (pinfunction "GND_1") (pintype "passive"))
      (node (ref "U9") (pin "3") (pinfunction "CE_3") (pintype "passive"))
    )
    (net (code "14") (name "Net-(C17-Pad2)") (class "Default")
      (node (ref "C17") (pin "2") (pinfunction "2_2") (pintype "passive"))
      (node (ref "R6") (pin "2") (pinfunction "2_2") (pintype "passive"))
      (node (ref "TR2") (pin "2") (pinfunction "2_2") (pintype "passive"))
    )
    (net (code "15") (name "Net-(C19-Pad1)") (class "Default")
      (node (ref "C19") (pin "1") (pinfunction "1_1") (pintype "passive"))
      (node (ref "R10") (pin "1") (pinfunction "1_1") (pintype "passive"))
      (node (ref "TR2") (pin "1") (pinfunction "1_1") (pintype "passive"))
    )
    (net (code "16") (name "Net-(C22-Pad2)") (class "Default")
      (node (ref "C22") (pin "2") (pinfunction "2_2") (pintype "passive"))
      (node (ref "R11") (pin "2") (pinfunction "2_2") (pintype "passive"))
      (node (ref "R12") (pin "1") (pinfunction "1_1") (pintype "passive"))
      (node (ref "TR3") (pin "2") (pinfunction "2_2") (pintype "passive"))
    )
    (net (code "17") (name "Net-(C24-Pad1)") (class "Default")
      (node (ref "C24") (pin "1") (pinfunction "1_1") (pintype "passive"))
      (node (ref "R13") (pin "2") (pinfunction "2_2") (pintype "passive"))
      (node (ref "R14") (pin "2") (pinfunction "2_2") (pintype "passive"))
      (node (ref "TR3") (pin "1") (pinfunction "1_1") (pintype "passive"))
    )
    (net (code "18") (name "Net-(C25-Pad2)") (class "Default")
      (node (ref "C25") (pin "2") (pinfunction "2_2") (pintype "passive"))
      (node (ref "C26") (pin "2") (pinfunction "2_2") (pintype "passive"))
      (node (ref "C29") (pin "1") (pinfunction "1_1") (pintype "passive"))
      (node (ref "D1") (pin "A") (pinfunction "A_A") (pintype "passive"))
      (node (ref "L1") (pin "2") (pinfunction "2_2") (pintype "passive"))
      (node (ref "R15") (pin "2") (pinfunction "2_2") (pintype "passive"))
    )
    (net (code "19") (name "Net-(C32-Pad2)") (class "Default")
      (node (ref "C32") (pin "2") (pinfunction "2_2") (pintype "passive"))
      (node (ref "D4") (pin "A") (pinfunction "A_A") (pintype "passive"))
      (node (ref "D5") (pin "K") (pinfunction "K_K") (pintype "passive"))
      (node (ref "F3") (pin "1") (pinfunction "1_1") (pintype "passive"))
    )
    (net (code "20") (name "Net-(CAB1-Pad1)") (class "Default")
      (node (ref "CAB1") (pin "1") (pinfunction "1_1") (pintype "passive"))
      (node (ref "CB_2") (pin "2") (pinfunction "2_2") (pintype "passive"))
      (node (ref "RB_2") (pin "1") (pinfunction "1_1") (pintype "passive"))
      (node (ref "RB_4") (pin "2") (pinfunction "2_2") (pintype "passive"))
    )
    (net (code "21") (name "Net-(CAB1-Pad2)") (class "Default")
      (node (ref "CAB1") (pin "2") (pinfunction "2_2") (pintype "passive"))
      (node (ref "CA_1") (pin "1") (pinfunction "1_1") (pintype "passive"))
      (node (ref "RA_1") (pin "2") (pinfunction "2_2") (pintype "passive"))
      (node (ref "RA_3") (pin "1") (pinfunction "1_1") (pintype "passive"))
    )
    (net (code "22") (name "Net-(CONN5-SIGNAL)") (class "Default")
      (node (ref "CONN5") (pin "1") (pinfunction "SIGNAL_1") (pintype "passive"))
      (node (ref "F2") (pin "2") (pinfunction "2_2") (pintype "passive"))
    )
    (net (code "23") (name "Net-(D6-PadA)") (class "Default")
      (node (ref "D6") (pin "A") (pinfunction "A_A") (pintype "passive"))
      (node (ref "R21") (pin "1") (pinfunction "1_1") (pintype "passive"))
    )
    (net (code "24") (name "Net-(F1-Pad1)") (class "Default")
      (node (ref "F1") (pin "1") (pinfunction "1_1") (pintype "passive"))
      (node (ref "RB_3") (pin "2") (pinfunction "2_2") (pintype "passive"))
    )
    (net (code "25") (name "Net-(FA_1-Pad1)") (class "Default")
      (node (ref "FA_1") (pin "1") (pinfunction "1_1") (pintype "passive"))
      (node (ref "RA_2") (pin "2") (pinfunction "2_2") (pintype "passive"))
    )
    (net (code "26") (name "Net-(L2-Pad2)") (class "Default")
      (node (ref "L2") (pin "2") (pinfunction "2_2") (pintype "passive"))
      (node (ref "R17") (pin "1") (pinfunction "1_1") (pintype "passive"))
    )
    (net (code "27") (name "Net-(L4-Pad2)") (class "Default")
      (node (ref "L4") (pin "2") (pinfunction "2_2") (pintype "passive"))
      (node (ref "R25") (pin "1") (pinfunction "1_1") (pintype "passive"))
    )
    (net (code "28") (name "Net-(R18-Pad2)") (class "Default")
      (node (ref "R18") (pin "2") (pinfunction "2_2") (pintype "passive"))
      (node (ref "R19") (pin "1") (pinfunction "1_1") (pintype "passive"))
    )
    (net (code "29") (name "Net-(R20-Pad1)") (class "Default")
      (node (ref "R20") (pin "1") (pinfunction "1_1") (pintype "passive"))
      (node (ref "R22") (pin "2") (pinfunction "2_2") (pintype "passive"))
      (node (ref "U7") (pin "2") (pinfunction "2_2") (pintype "passive"))
    )
    (net (code "30") (name "Net-(R23-Pad1)") (class "Default")
      (node (ref "R23") (pin "1") (pinfunction "1_1") (pintype "passive"))
      (node (ref "R24") (pin "2") (pinfunction "2_2") (pintype "passive"))
      (node (ref "U8") (pin "2") (pinfunction "2_2") (pintype "passive"))
    )
    (net (code "31") (name "Net-(R26-Pad2)") (class "Default")
      (node (ref "R26") (pin "2") (pinfunction "2_2") (pintype "passive"))
      (node (ref "R27") (pin "1") (pinfunction "1_1") (pintype "passive"))
    )
    (net (code "32") (name "Net-(RA_4-Pad1)") (class "Default")
      (node (ref "RA_4") (pin "1") (pinfunction "1_1") (pintype "passive"))
      (node (ref "TR1") (pin "2") (pinfunction "2_2") (pintype "passive"))
    )
    (net (code "33") (name "Net-(RB_1-Pad2)") (class "Default")
      (node (ref "RB_1") (pin "2") (pinfunction "2_2") (pintype "passive"))
      (node (ref "TR1") (pin "1") (pinfunction "1_1") (pintype "passive"))
    )
    (net (code "34") (name "Net-(RPB_1-Pad2)") (class "Default")
      (node (ref "RPB_1") (pin "2") (pinfunction "2_2") (pintype "passive"))
      (node (ref "RPB_2") (pin "1") (pinfunction "1_1") (pintype "passive"))
    )
    (net (code "35") (name "Net-(SW1A-COM1)") (class "Default")
      (node (ref "CA_2") (pin "1") (pinfunction "1_1") (pintype "passive"))
      (node (ref "DA_1") (pin "K") (pinfunction "K_K") (pintype "passive"))
      (node (ref "FA_1") (pin "2") (pinfunction "2_2") (pintype "passive"))
      (node (ref "SW1") (pin "2") (pinfunction "COM1_2") (pintype "passive"))
    )
    (net (code "36") (name "Net-(SW1B-COM2)") (class "Default")
      (node (ref "CB_1") (pin "1") (pinfunction "1_1") (pintype "passive"))
      (node (ref "DB_1") (pin "A") (pinfunction "A_A") (pintype "passive"))
      (node (ref "F1") (pin "2") (pinfunction "2_2") (pintype "passive"))
      (node (ref "SW1") (pin "5") (pinfunction "COM2_5") (pintype "passive"))
    )
    (net (code "37") (name "Net-(SW2A-NC1)") (class "Default")
      (node (ref "RB_4") (pin "1") (pinfunction "1_1") (pintype "passive"))
      (node (ref "SW2") (pin "1") (pinfunction "NC1_1") (pintype "passive"))
    )
    (net (code "38") (name "Net-(SW2B-NC6)") (class "Default")
      (node (ref "RA_1") (pin "1") (pinfunction "1_1") (pintype "passive"))
      (node (ref "SW2") (pin "6") (pinfunction "NC6_6") (pintype "passive"))
    )
    (net (code "39") (name "Net-(SW3-NC1)") (class "Default")
      (node (ref "RG3") (pin "1") (pinfunction "1_1") (pintype "passive"))
      (node (ref "SW3") (pin "1") (pinfunction "NC1_1") (pintype "passive"))
    )
    (net (code "40") (name "Net-(SW3-NO1)") (class "Default")
      (node (ref "RG2") (pin "1") (pinfunction "1_1") (pintype "passive"))
      (node (ref "SW3") (pin "3") (pinfunction "NO1_3") (pintype "passive"))
    )
    (net (code "41") (name "Net-(SW3-NO2)") (class "Default")
      (node (ref "RG1") (pin "1") (pinfunction "1_1") (pintype "passive"))
      (node (ref "SW3") (pin "4") (pinfunction "NO2_4") (pintype "passive"))
    )
    (net (code "42") (name "Net-(SW4A-COM1)") (class "Default")
      (node (ref "SW4") (pin "2") (pinfunction "COM1_2") (pintype "passive"))
      (node (ref "U2") (pin "3") (pinfunction "RG_3") (pintype "passive"))
    )
    (net (code "43") (name "Net-(SW4A-NC1)") (class "Default")
      (node (ref "RG4") (pin "2") (pinfunction "2_2") (pintype "passive"))
      (node (ref "SW4") (pin "1") (pinfunction "NC1_1") (pintype "passive"))
    )
    (net (code "44") (name "Net-(SW4B-COM2)") (class "Default")
      (node (ref "SW4") (pin "5") (pinfunction "COM2_5") (pintype "passive"))
      (node (ref "U2") (pin "2") (pinfunction "RG_2") (pintype "passive"))
    )
    (net (code "45") (name "Net-(SW4B-NC2)") (class "Default")
      (node (ref "RG4") (pin "1") (pinfunction "1_1") (pintype "passive"))
      (node (ref "SW4") (pin "4") (pinfunction "NC2_4") (pintype "passive"))
    )
    (net (code "46") (name "Net-(SW5A-NC1)") (class "Default")
      (node (ref "RPB_2") (pin "2") (pinfunction "2_2") (pintype "passive"))
      (node (ref "RPB_3") (pin "1") (pinfunction "1_1") (pintype "passive"))
      (node (ref "SW5") (pin "1") (pinfunction "NC1_1") (pintype "passive"))
    )
    (net (code "47") (name "Net-(SW5A-NC2)") (class "Default")
      (node (ref "C6") (pin "2") (pinfunction "2_2") (pintype "passive"))
      (node (ref "SW5") (pin "2") (pinfunction "NC2_2") (pintype "passive"))
    )
    (net (code "48") (name "Net-(SW5A-NO1)") (class "Default")
      (node (ref "C7") (pin "2") (pinfunction "2_2") (pintype "passive"))
      (node (ref "SW5") (pin "3") (pinfunction "NO1_3") (pintype "passive"))
    )
    (net (code "49") (name "Net-(SW5A-NO2)") (class "Default")
      (node (ref "C8") (pin "2") (pinfunction "2_2") (pintype "passive"))
      (node (ref "SW5") (pin "4") (pinfunction "NO2_4") (pintype "passive"))
    )
    (net (code "50") (name "Net-(SW5A-NO3)") (class "Default")
      (node (ref "C10") (pin "2") (pinfunction "2_2") (pintype "passive"))
      (node (ref "C11") (pin "2") (pinfunction "2_2") (pintype "passive"))
      (node (ref "C9") (pin "2") (pinfunction "2_2") (pintype "passive"))
      (node (ref "SW5") (pin "5") (pinfunction "NO3_5") (pintype "passive"))
    )
    (net (code "51") (name "Net-(SW5B-NC6)") (class "Default")
      (node (ref "RPB_3") (pin "2") (pinfunction "2_2") (pintype "passive"))
      (node (ref "SW5") (pin "6") (pinfunction "NC6_6") (pintype "passive"))
      (node (ref "U1") (pin "3") (pinfunction "+_3") (pintype "passive"))
    )
    (net (code "52") (name "Net-(SW5B-NO5)") (class "Default")
      (node (ref "C12") (pin "2") (pinfunction "2_2") (pintype "passive"))
      (node (ref "SW5") (pin "7") (pinfunction "NO5_7") (pintype "passive"))
    )
    (net (code "53") (name "Net-(SW5B-NO6)") (class "Default")
      (node (ref "C13") (pin "2") (pinfunction "2_2") (pintype "passive"))
      (node (ref "SW5") (pin "8") (pinfunction "NO6_8") (pintype "passive"))
    )
    (net (code "54") (name "Net-(SW5B-NO7)") (class "Default")
      (node (ref "C14") (pin "2") (pinfunction "2_2") (pintype "passive"))
      (node (ref "SW5") (pin "9") (pinfunction "NO7_9") (pintype "passive"))
    )
    (net (code "55") (name "Net-(SW5B-NO8)") (class "Default")
      (node (ref "C15") (pin "2") (pinfunction "2_2") (pintype "passive"))
      (node (ref "SW5") (pin "10") (pinfunction "NO8_10") (pintype "passive"))
    )
    (net (code "56") (name "Net-(SW6B-COM2)") (class "Default")
      (node (ref "C21") (pin "2") (pinfunction "2_2") (pintype "passive"))
      (node (ref "SW6") (pin "5") (pinfunction "COM2_5") (pintype "passive"))
      (node (ref "U3") (pin "3") (pinfunction "+_3") (pintype "passive"))
    )
    (net (code "57") (name "Net-(SW7A-COM1)") (class "Default")
      (node (ref "D1") (pin "K") (pinfunction "K_K") (pintype "passive"))
      (node (ref "D4") (pin "K") (pinfunction "K_K") (pintype "passive"))
      (node (ref "SW7") (pin "2") (pinfunction "COM1_2") (pintype "passive"))
    )
    (net (code "58") (name "Net-(SW7A-NO1)") (class "Default")
      (node (ref "C37") (pin "2") (pinfunction "2_2") (pintype "passive"))
      (node (ref "C38") (pin "2") (pinfunction "2_2") (pintype "passive"))
      (node (ref "L3") (pin "1") (pinfunction "1_1") (pintype "passive"))
      (node (ref "SW7") (pin "3") (pinfunction "NO1_3") (pintype "passive"))
      (node (ref "TP7") (pin "1") (pinfunction "1_1") (pintype "passive"))
    )
    (net (code "59") (name "Net-(U1--)") (class "Default")
      (node (ref "C2") (pin "1") (pinfunction "1_1") (pintype "passive"))
      (node (ref "R1") (pin "1") (pinfunction "1_1") (pintype "passive"))
      (node (ref "RG1") (pin "2") (pinfunction "2_2") (pintype "passive"))
      (node (ref "RG2") (pin "2") (pinfunction "2_2") (pintype "passive"))
      (node (ref "RG3") (pin "2") (pinfunction "2_2") (pintype "passive"))
      (node (ref "U1") (pin "2") (pinfunction "-_2") (pintype "passive"))
    )
    (net (code "60") (name "Net-(U1-Out)") (class "Default")
      (node (ref "C2") (pin "2") (pinfunction "2_2") (pintype "passive"))
      (node (ref "R1") (pin "2") (pinfunction "2_2") (pintype "passive"))
      (node (ref "R5") (pin "1") (pinfunction "1_1") (pintype "passive"))
      (node (ref "U1") (pin "6") (pinfunction "Out_6") (pintype "output"))
    )
    (net (code "61") (name "Net-(U2-IN+)") (class "Default")
      (node (ref "QB_1") (pin "1") (pinfunction "1_1") (pintype "passive"))
      (node (ref "QB_2") (pin "2") (pinfunction "2_2") (pintype "passive"))
      (node (ref "QB_2") (pin "3") (pinfunction "3_3") (pintype "passive"))
      (node (ref "RB_2") (pin "2") (pinfunction "2_2") (pintype "passive"))
      (node (ref "U2") (pin "4") (pinfunction "IN+_4") (pintype "tri_state"))
    )
    (net (code "62") (name "Net-(U2-IN-)") (class "Default")
      (node (ref "QA_1") (pin "1") (pinfunction "1_1") (pintype "passive"))
      (node (ref "QA_2") (pin "2") (pinfunction "2_2") (pintype "passive"))
      (node (ref "QA_2") (pin "3") (pinfunction "3_3") (pintype "passive"))
      (node (ref "RA_3") (pin "2") (pinfunction "2_2") (pintype "passive"))
      (node (ref "U2") (pin "1") (pinfunction "IN-_1") (pintype "tri_state"))
    )
    (net (code "63") (name "Net-(U2-Out)") (class "Default")
      (node (ref "RPB_1") (pin "1") (pinfunction "1_1") (pintype "passive"))
      (node (ref "U2") (pin "7") (pinfunction "Out_7") (pintype "output"))
    )
    (net (code "64") (name "Net-(U3--)") (class "Default")
      (node (ref "C16") (pin "1") (pinfunction "1_1") (pintype "passive"))
      (node (ref "R7") (pin "1") (pinfunction "1_1") (pintype "passive"))
      (node (ref "R8") (pin "2") (pinfunction "2_2") (pintype "passive"))
      (node (ref "U3") (pin "2") (pinfunction "-_2") (pintype "passive"))
    )
    (net (code "65") (name "Net-(U3-Out)") (class "Default")
      (node (ref "R9") (pin "1") (pinfunction "1_1") (pintype "passive"))
      (node (ref "U3") (pin "6") (pinfunction "Out_6") (pintype "output"))
    )
    (net (code "66") (name "Net-(U4-Bst)") (class "Default")
      (node (ref "C23") (pin "2") (pinfunction "2_2") (pintype "passive"))
      (node (ref "U4") (pin "1") (pinfunction "Bst_1") (pintype "passive"))
    )
    (net (code "67") (name "Net-(U4-FB)") (class "Default")
      (node (ref "C29") (pin "2") (pinfunction "2_2") (pintype "passive"))
      (node (ref "R15") (pin "1") (pinfunction "1_1") (pintype "passive"))
      (node (ref "R16") (pin "2") (pinfunction "2_2") (pintype "passive"))
      (node (ref "U4") (pin "3") (pinfunction "FB_3") (pintype "passive"))
    )
    (net (code "68") (name "Net-(U4-Lx)") (class "Default")
      (node (ref "C23") (pin "1") (pinfunction "1_1") (pintype "passive"))
      (node (ref "D2") (pin "K") (pinfunction "K_K") (pintype "passive"))
      (node (ref "L1") (pin "1") (pinfunction "1_1") (pintype "passive"))
      (node (ref "U4") (pin "6") (pinfunction "Lx_6") (pintype "passive"))
    )
    (net (code "69") (name "Net-(U5-Vin)") (class "Default")
      (node (ref "C34") (pin "2") (pinfunction "2_2") (pintype "passive"))
      (node (ref "C35") (pin "2") (pinfunction "2_2") (pintype "passive"))
      (node (ref "R17") (pin "2") (pinfunction "2_2") (pintype "passive"))
      (node (ref "TP4") (pin "1") (pinfunction "1_1") (pintype "passive"))
      (node (ref "U5") (pin "1") (pinfunction "Vin_1") (pintype "passive"))
    )
    (net (code "70") (name "Net-(U6-+Vin)") (class "Default")
      (node (ref "C30") (pin "2") (pinfunction "2_2") (pintype "passive"))
      (node (ref "L3") (pin "2") (pinfunction "2_2") (pintype "passive"))
      (node (ref "U6") (pin "2") (pinfunction "+Vin_2") (pintype "passive"))
    )
    (net (code "71") (name "Net-(U6-+Vout)") (class "Default")
      (node (ref "C33") (pin "2") (pinfunction "2_2") (pintype "passive"))
      (node (ref "L2") (pin "1") (pinfunction "1_1") (pintype "passive"))
      (node (ref "U6") (pin "8") (pinfunction "+Vout_8") (pintype "power_in"))
    )
    (net (code "72") (name "Net-(U6--Vout)") (class "Default")
      (node (ref "C39") (pin "1") (pinfunction "1_1") (pintype "passive"))
      (node (ref "L4") (pin "1") (pinfunction "1_1") (pintype "passive"))
      (node (ref "U6") (pin "6") (pinfunction "-Vout_6") (pintype "passive"))
    )
    (net (code "73") (name "Net-(U9--Vin)") (class "Default")
      (node (ref "C40") (pin "1") (pinfunction "1_1") (pintype "passive"))
      (node (ref "C41") (pin "1") (pinfunction "1_1") (pintype "passive"))
      (node (ref "R25") (pin "2") (pinfunction "2_2") (pintype "passive"))
      (node (ref "TP13") (pin "1") (pinfunction "1_1") (pintype "passive"))
      (node (ref "U9") (pin "2") (pinfunction "-Vin_2") (pintype "passive"))
    )
    (net (code "74") (name "PGND") (class "Default")
      (node (ref "C25") (pin "1") (pinfunction "1_1") (pintype "passive"))
      (node (ref "C26") (pin "1") (pinfunction "1_1") (pintype "passive"))
      (node (ref "C28") (pin "1") (pinfunction "1_1") (pintype "passive"))
      (node (ref "C32") (pin "1") (pinfunction "1_1") (pintype "passive"))
      (node (ref "D2") (pin "A") (pinfunction "A_A") (pintype "passive"))
      (node (ref "D5") (pin "A") (pinfunction "A_A") (pintype "passive"))
      (node (ref "JP1") (pin "A1") (pinfunction "GND_A1") (pintype "passive"))
      (node (ref "JP1") (pin "A12") (pinfunction "GND_A12") (pintype "passive"))
      (node (ref "JP1") (pin "B1") (pinfunction "GND_B1") (pintype "passive"))
      (node (ref "JP1") (pin "B12") (pinfunction "GND_B12") (pintype "passive"))
      (node (ref "JP1") (pin "SH") (pinfunction "SH_SH") (pintype "passive"))
      (node (ref "Q1") (pin "2") (pinfunction "S_2") (pintype "passive"))
      (node (ref "R16") (pin "1") (pinfunction "1_1") (pintype "passive"))
      (node (ref "SW7") (pin "5") (pinfunction "COM2_5") (pintype "passive"))
      (node (ref "U4") (pin "2") (pinfunction "GND_2") (pintype "passive"))
    )
    (net (code "75") (name "PriGND") (class "Default")
      (node (ref "C37") (pin "1") (pinfunction "1_1") (pintype "passive"))
      (node (ref "C38") (pin "1") (pinfunction "1_1") (pintype "passive"))
      (node (ref "SW7") (pin "6") (pinfunction "NO2_6") (pintype "passive"))
      (node (ref "TP10") (pin "1") (pinfunction "1_1") (pintype "passive"))
      (node (ref "U6") (pin "1") (pinfunction "-Vin_1") (pintype "passive"))
    )
    (net (code "76") (name "VCC_USB") (class "Default")
      (node (ref "F3") (pin "2") (pinfunction "2_2") (pintype "passive"))
      (node (ref "JP1") (pin "A4") (pinfunction "+V_A4") (pintype "passive"))
      (node (ref "JP1") (pin "A9") (pinfunction "+V_A9") (pintype "passive"))
      (node (ref "JP1") (pin "B4") (pinfunction "+V_B4") (pintype "passive"))
      (node (ref "JP1") (pin "B9") (pinfunction "+V_B9") (pintype "passive"))
      (node (ref "TP6") (pin "1") (pinfunction "1_1") (pintype "passive"))
    )
    (net (code "77") (name "Vcc") (class "Default")
      (node (ref "C1") (pin "2") (pinfunction "2_2") (pintype "passive"))
      (node (ref "C18") (pin "2") (pinfunction "2_2") (pintype "passive"))
      (node (ref "C3") (pin "2") (pinfunction "2_2") (pintype "passive"))
      (node (ref "C36") (pin "2") (pinfunction "2_2") (pintype "passive"))
      (node (ref "QA_1") (pin "2") (pinfunction "2_2") (pintype "passive"))
      (node (ref "QA_1") (pin "3") (pinfunction "3_3") (pintype "passive"))
      (node (ref "QB_1") (pin "2") (pinfunction "2_2") (pintype "passive"))
      (node (ref "QB_1") (pin "3") (pinfunction "3_3") (pintype "passive"))
      (node (ref "R18") (pin "1") (pinfunction "1_1") (pintype "passive"))
      (node (ref "R21") (pin "2") (pinfunction "2_2") (pintype "passive"))
      (node (ref "TP8") (pin "1") (pinfunction "1_1") (pintype "passive"))
      (node (ref "U1") (pin "7") (pinfunction "Vcc_7") (pintype "power_in"))
      (node (ref "U2") (pin "8") (pinfunction "Vcc_8") (pintype "power_in"))
      (node (ref "U3") (pin "7") (pinfunction "Vcc_7") (pintype "power_in"))
      (node (ref "U5") (pin "5") (pinfunction "Vout_5") (pintype "power_in"))
    )
    (net (code "78") (name "Vee") (class "Default")
      (node (ref "C20") (pin "2") (pinfunction "2_2") (pintype "passive"))
      (node (ref "C4") (pin "2") (pinfunction "2_2") (pintype "passive"))
      (node (ref "C42") (pin "1") (pinfunction "1_1") (pintype "passive"))
      (node (ref "C5") (pin "2") (pinfunction "2_2") (pintype "passive"))
      (node (ref "QA_2") (pin "1") (pinfunction "1_1") (pintype "passive"))
      (node (ref "QB_2") (pin "1") (pinfunction "1_1") (pintype "passive"))
      (node (ref "R26") (pin "1") (pinfunction "1_1") (pintype "passive"))
      (node (ref "TP11") (pin "1") (pinfunction "1_1") (pintype "passive"))
      (node (ref "U1") (pin "4") (pinfunction "Vee_4") (pintype "power_in"))
      (node (ref "U2") (pin "5") (pinfunction "Vee_5") (pintype "power_in"))
      (node (ref "U3") (pin "4") (pinfunction "Vee_4") (pintype "power_in"))
      (node (ref "U9") (pin "5") (pinfunction "-Vout_5") (pintype "passive"))
    )
    (net (code "79") (name "unconnected-(CONN5-Pad3)") (class "Default")
      (node (ref "CONN5") (pin "3") (pinfunction "3_3") (pintype "passive+no_connect"))
    )
    (net (code "80") (name "unconnected-(FID1-Pad5)") (class "Default")
      (node (ref "FID1") (pin "5") (pinfunction "5_5") (pintype "passive"))
    )
    (net (code "81") (name "unconnected-(FID2-Pad5)") (class "Default")
      (node (ref "FID2") (pin "5") (pinfunction "5_5") (pintype "passive"))
    )
    (net (code "82") (name "unconnected-(FID3-Pad5)") (class "Default")
      (node (ref "FID3") (pin "5") (pinfunction "5_5") (pintype "passive"))
    )
    (net (code "83") (name "unconnected-(JP1-CC1-PadA5)") (class "Default")
      (node (ref "JP1") (pin "A5") (pinfunction "CC1_A5") (pintype "passive+no_connect"))
    )
    (net (code "84") (name "unconnected-(JP1-CC2-PadB5)") (class "Default")
      (node (ref "JP1") (pin "B5") (pinfunction "CC2_B5") (pintype "passive+no_connect"))
    )
    (net (code "85") (name "unconnected-(JP1-D+-PadA6)") (class "Default")
      (node (ref "JP1") (pin "A6") (pinfunction "D+_A6") (pintype "passive+no_connect"))
    )
    (net (code "86") (name "unconnected-(JP1-D+-PadB6)") (class "Default")
      (node (ref "JP1") (pin "B6") (pinfunction "D+_B6") (pintype "passive+no_connect"))
    )
    (net (code "87") (name "unconnected-(JP1-D--PadA7)") (class "Default")
      (node (ref "JP1") (pin "A7") (pinfunction "D-_A7") (pintype "passive+no_connect"))
    )
    (net (code "88") (name "unconnected-(JP1-D--PadB7)") (class "Default")
      (node (ref "JP1") (pin "B7") (pinfunction "D-_B7") (pintype "passive+no_connect"))
    )
    (net (code "89") (name "unconnected-(JP1-RX1+-PadB11)") (class "Default")
      (node (ref "JP1") (pin "B11") (pinfunction "RX1+_B11") (pintype "passive+no_connect"))
    )
    (net (code "90") (name "unconnected-(JP1-RX1--PadB10)") (class "Default")
      (node (ref "JP1") (pin "B10") (pinfunction "RX1-_B10") (pintype "passive+no_connect"))
    )
    (net (code "91") (name "unconnected-(JP1-RX2+-PadA11)") (class "Default")
      (node (ref "JP1") (pin "A11") (pinfunction "RX2+_A11") (pintype "passive+no_connect"))
    )
    (net (code "92") (name "unconnected-(JP1-RX2--PadA10)") (class "Default")
      (node (ref "JP1") (pin "A10") (pinfunction "RX2-_A10") (pintype "passive+no_connect"))
    )
    (net (code "93") (name "unconnected-(JP1-SBU1-PadA8)") (class "Default")
      (node (ref "JP1") (pin "A8") (pinfunction "SBU1_A8") (pintype "passive+no_connect"))
    )
    (net (code "94") (name "unconnected-(JP1-SBU2-PadB8)") (class "Default")
      (node (ref "JP1") (pin "B8") (pinfunction "SBU2_B8") (pintype "passive+no_connect"))
    )
    (net (code "95") (name "unconnected-(JP1-TX1+-PadA2)") (class "Default")
      (node (ref "JP1") (pin "A2") (pinfunction "TX1+_A2") (pintype "passive+no_connect"))
    )
    (net (code "96") (name "unconnected-(JP1-TX1--PadA3)") (class "Default")
      (node (ref "JP1") (pin "A3") (pinfunction "TX1-_A3") (pintype "passive+no_connect"))
    )
    (net (code "97") (name "unconnected-(JP1-TX2+-PadB2)") (class "Default")
      (node (ref "JP1") (pin "B2") (pinfunction "TX2+_B2") (pintype "passive+no_connect"))
    )
    (net (code "98") (name "unconnected-(JP1-TX2--PadB3)") (class "Default")
      (node (ref "JP1") (pin "B3") (pinfunction "TX2-_B3") (pintype "passive+no_connect"))
    )
    (net (code "99") (name "unconnected-(MS-Pad5)") (class "Default")
      (node (ref "MS") (pin "5") (pinfunction "5_5") (pintype "passive"))
    )
    (net (code "100") (name "unconnected-(MS1-Pad5)") (class "Default")
      (node (ref "MS1") (pin "5") (pinfunction "5_5") (pintype "passive"))
    )
    (net (code "101") (name "unconnected-(MS2-Pad5)") (class "Default")
      (node (ref "MS2") (pin "5") (pinfunction "5_5") (pintype "passive"))
    )
    (net (code "102") (name "unconnected-(MS3-Pad5)") (class "Default")
      (node (ref "MS3") (pin "5") (pinfunction "5_5") (pintype "passive"))
    )
    (net (code "103") (name "unconnected-(SW1A-NO1-Pad3)") (class "Default")
      (node (ref "SW1") (pin "3") (pinfunction "NO1_3") (pintype "passive+no_connect"))
    )
    (net (code "104") (name "unconnected-(SW1B-NO2-Pad6)") (class "Default")
      (node (ref "SW1") (pin "6") (pinfunction "NO2_6") (pintype "passive+no_connect"))
    )
    (net (code "105") (name "unconnected-(SW4A-NO1-Pad3)") (class "Default")
      (node (ref "SW4") (pin "3") (pinfunction "NO1_3") (pintype "passive+no_connect"))
    )
    (net (code "106") (name "unconnected-(SW4B-NO2-Pad6)") (class "Default")
      (node (ref "SW4") (pin "6") (pinfunction "NO2_6") (pintype "passive+no_connect"))
    )
    (net (code "107") (name "unconnected-(SW6A-COM1-Pad2)") (class "Default")
      (node (ref "SW6") (pin "2") (pinfunction "COM1_2") (pintype "passive+no_connect"))
    )
    (net (code "108") (name "unconnected-(SW6A-NC1-Pad1)") (class "Default")
      (node (ref "SW6") (pin "1") (pinfunction "NC1_1") (pintype "passive+no_connect"))
    )
    (net (code "109") (name "unconnected-(SW6A-NO1-Pad3)") (class "Default")
      (node (ref "SW6") (pin "3") (pinfunction "NO1_3") (pintype "passive+no_connect"))
    )
    (net (code "110") (name "unconnected-(SW7A-NC1-Pad1)") (class "Default")
      (node (ref "SW7") (pin "1") (pinfunction "NC1_1") (pintype "passive"))
    )
    (net (code "111") (name "unconnected-(SW7B-NC2-Pad4)") (class "Default")
      (node (ref "SW7") (pin "4") (pinfunction "NC2_4") (pintype "passive"))
    )
    (net (code "112") (name "unconnected-(U5-NC-Pad3)") (class "Default")
      (node (ref "U5") (pin "3") (pinfunction "NC_3") (pintype "passive+no_connect"))
    )
    (net (code "113") (name "unconnected-(U5-NC-Pad4)") (class "Default")
      (node (ref "U5") (pin "4") (pinfunction "NC_4") (pintype "passive+no_connect"))
    )
    (net (code "114") (name "unconnected-(U9-NC-Pad4)") (class "Default")
      (node (ref "U9") (pin "4") (pinfunction "NC_4") (pintype "passive+no_connect"))
    )
  )
)
